# Schematic_-_EasyEDA.net
KiCad netlist of a schematic drawn in EasyEDA
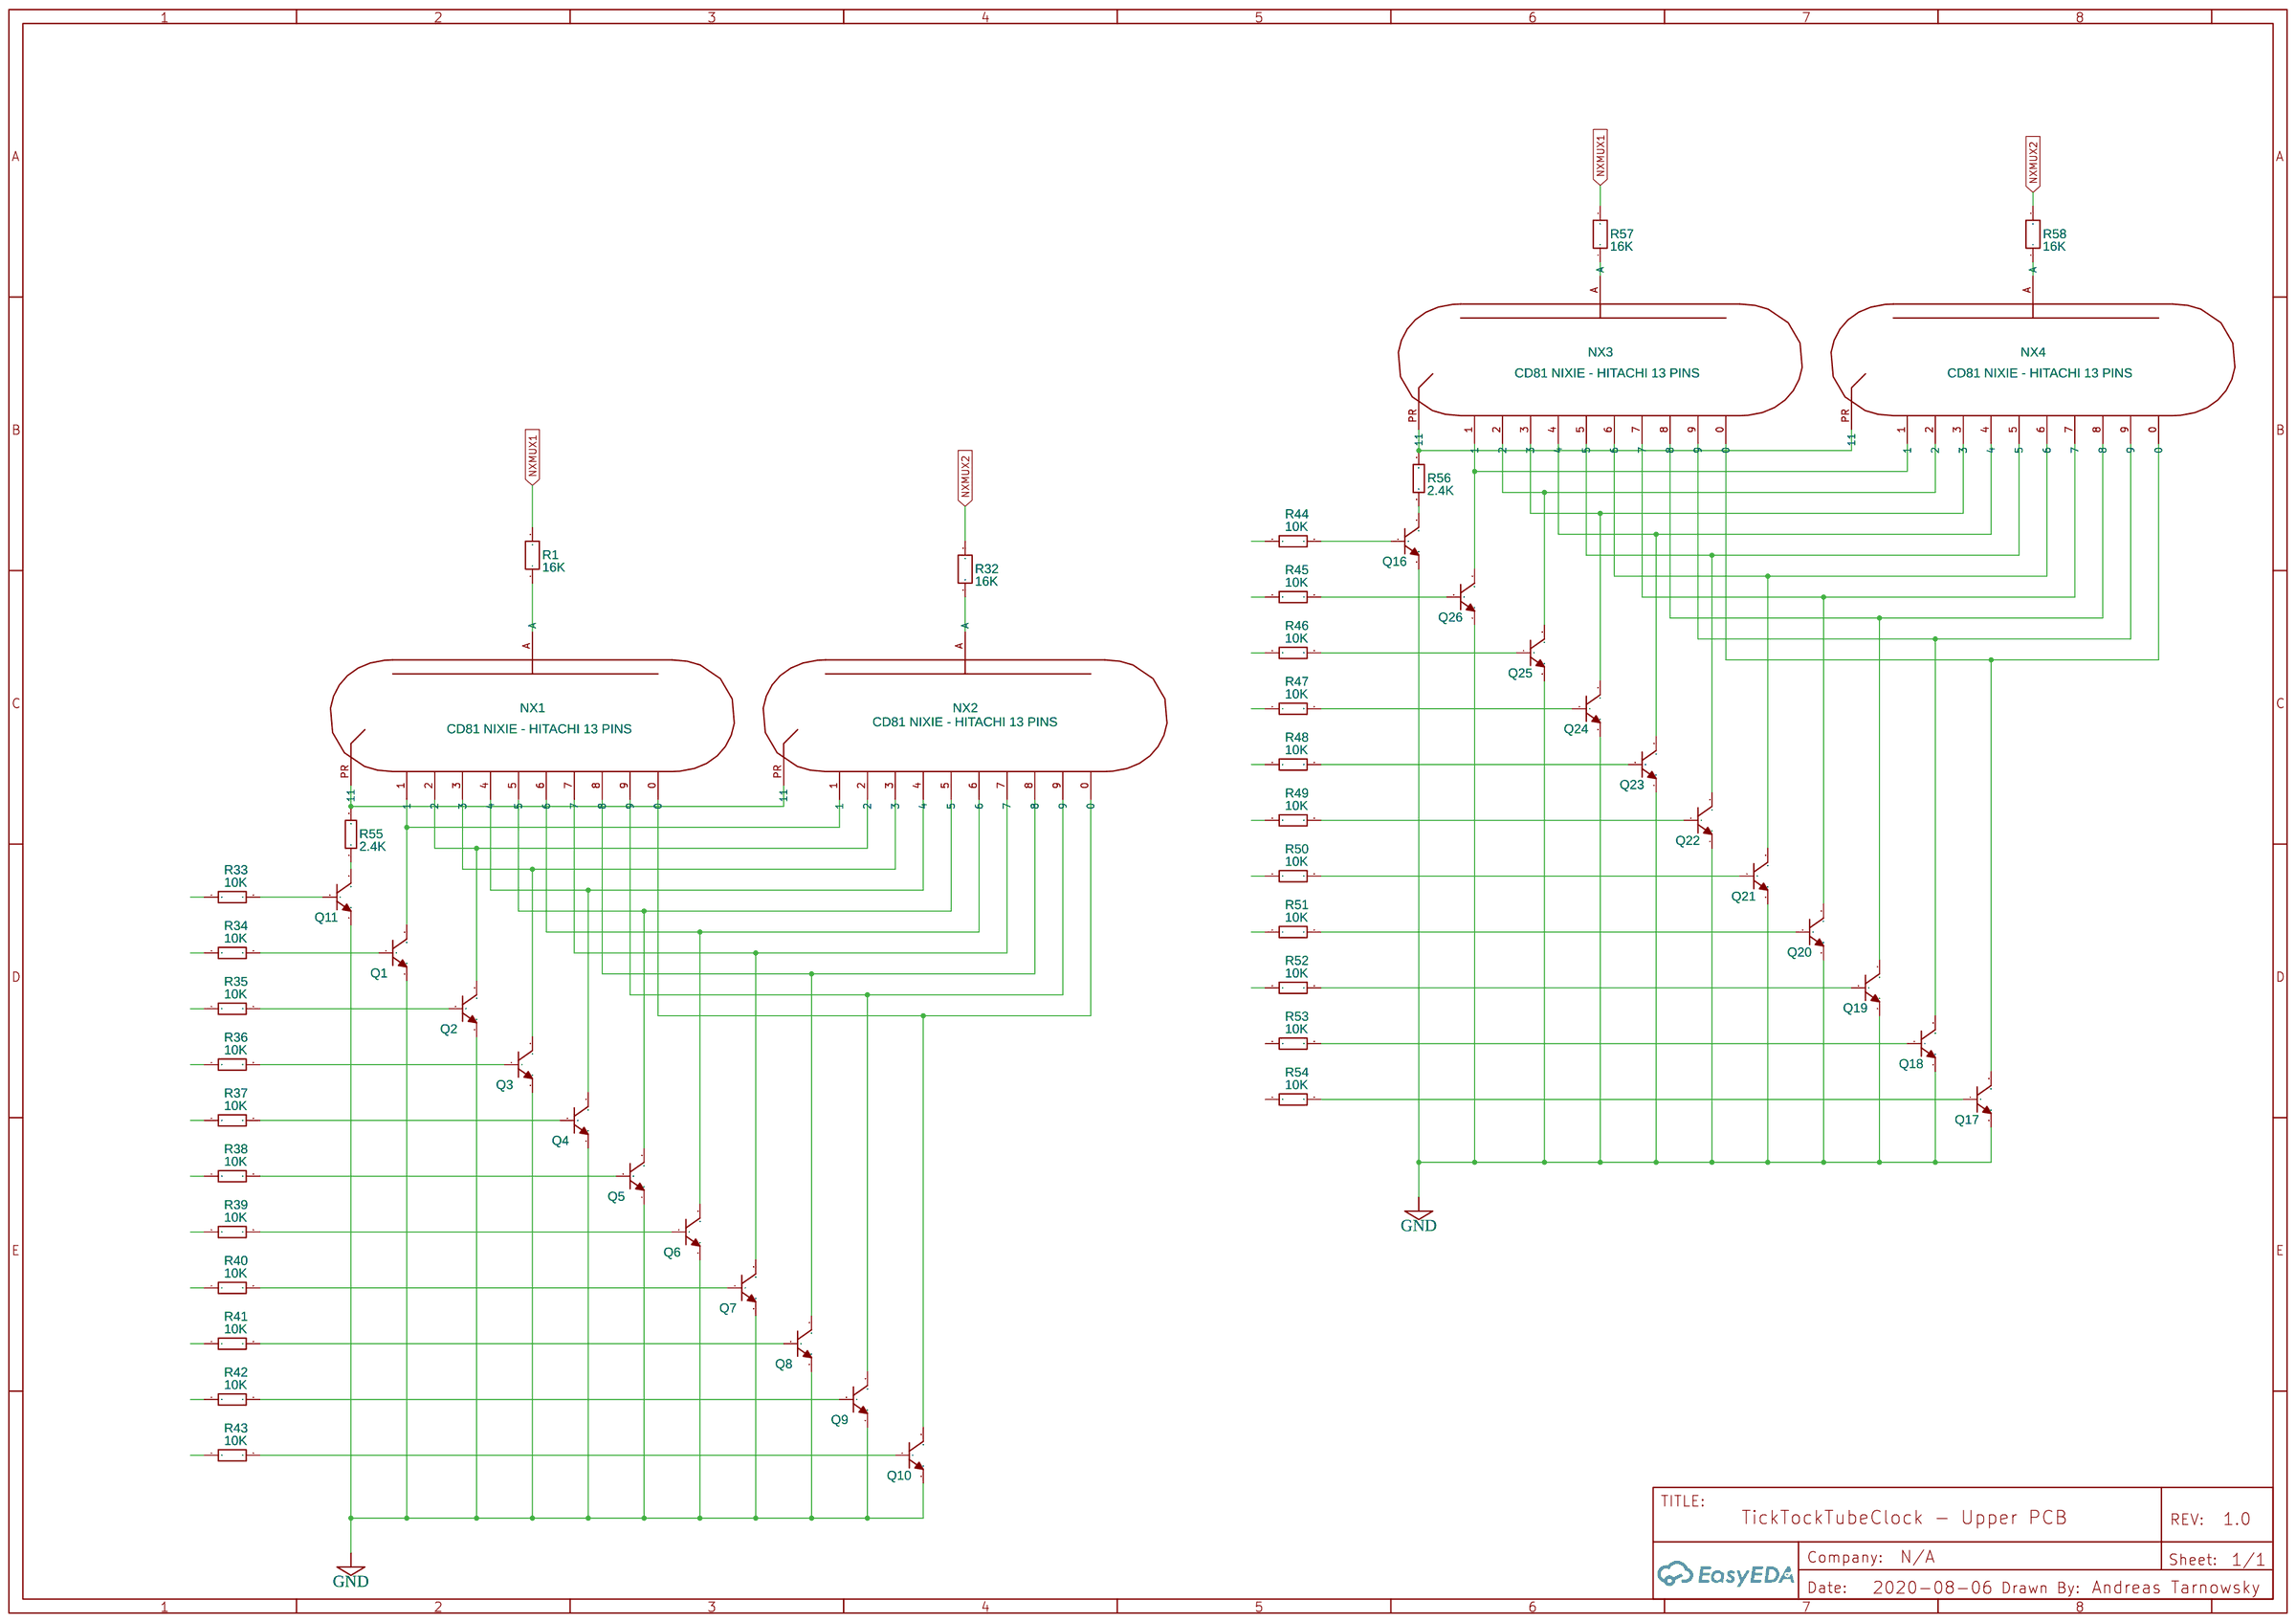
[diagram p0: Upper Schematic]
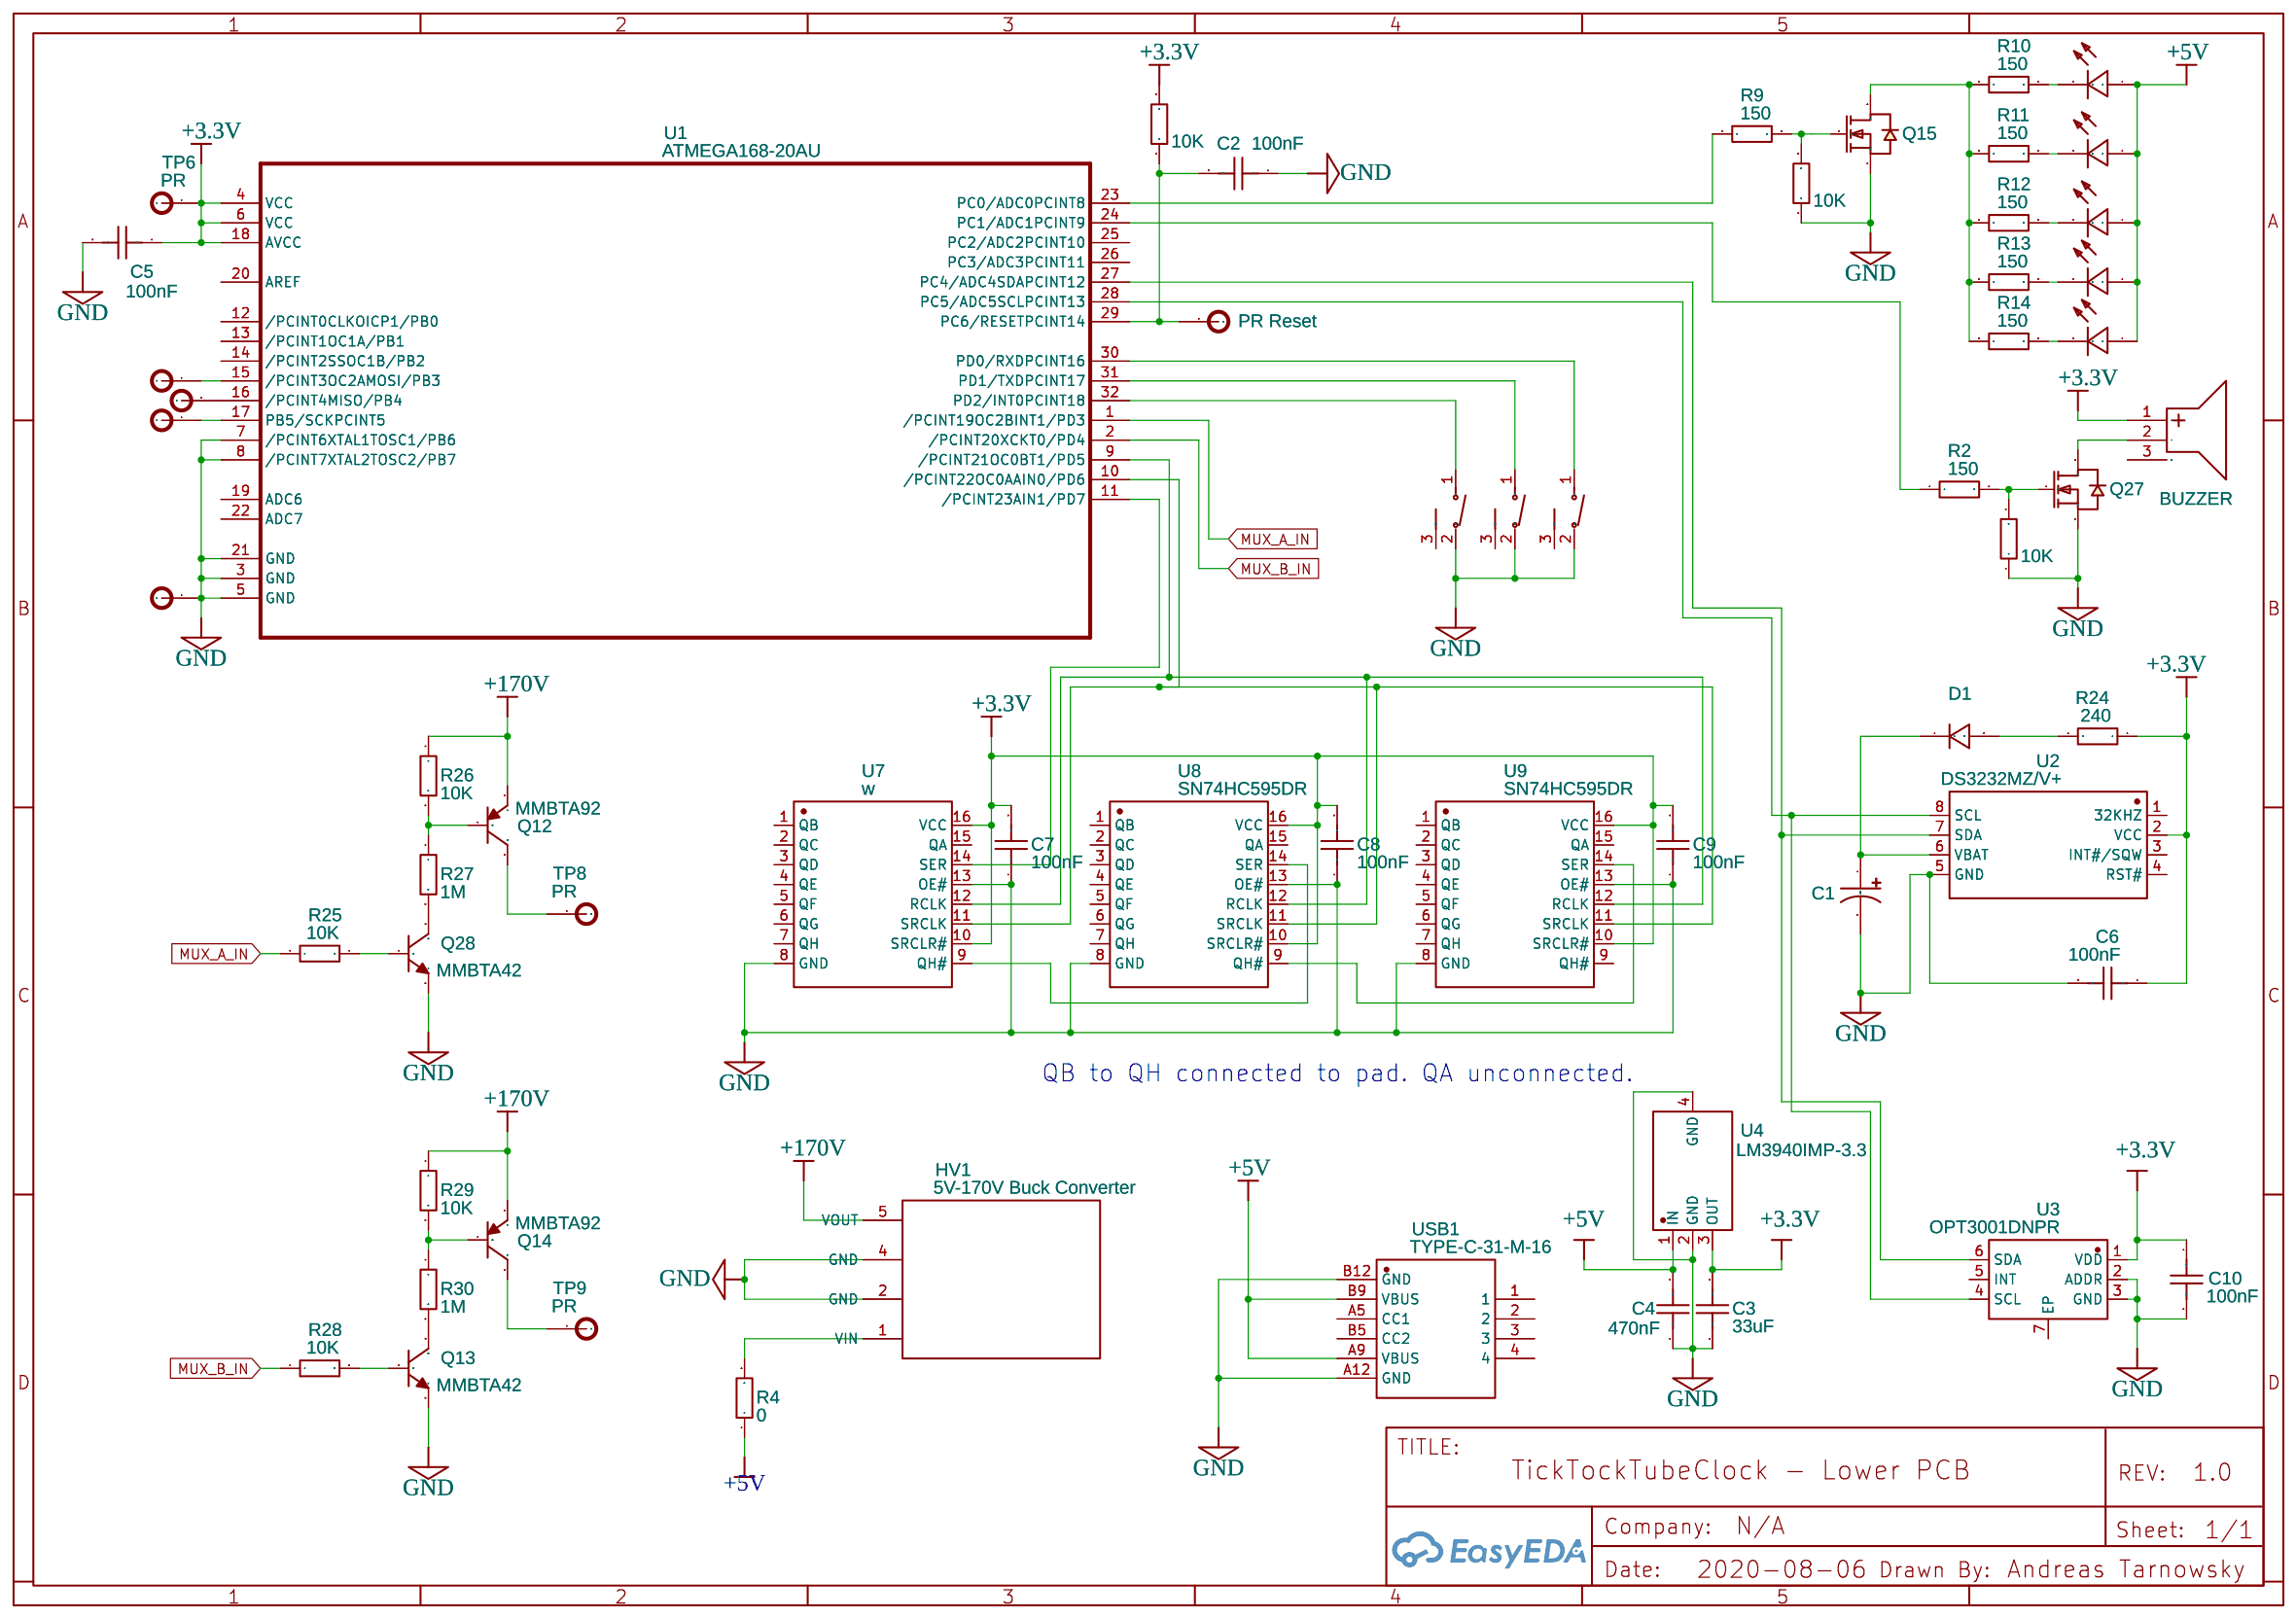
[diagram p1: Lower Schematic]

(export (version "E")
  (design (tool "Eeschema 10.0.6"))
  (components
    (comp (ref "NX1")
      (value "CD81 NIXIE - HITACHI 13 PINS")
      (libsource (lib "") (part "CD81 NIXIE - HITACHI 13 PINS"))
    )
    (comp (ref "NX2")
      (value "CD81 NIXIE - HITACHI 13 PINS")
      (libsource (lib "") (part "CD81 NIXIE - HITACHI 13 PINS"))
    )
    (comp (ref "NX3")
      (value "CD81 NIXIE - HITACHI 13 PINS")
      (libsource (lib "") (part "CD81 NIXIE - HITACHI 13 PINS"))
    )
    (comp (ref "NX4")
      (value "CD81 NIXIE - HITACHI 13 PINS")
      (libsource (lib "") (part "CD81 NIXIE - HITACHI 13 PINS"))
    )
    (comp (ref "Q1")
      (value "MMBTA42")
      (fields
        (field (name "BOM_Manufacturer Part") "MMBTA42LT1G")
        (field (name "BOM_Supplier Part") "C94389")
      )
      (libsource (lib "") (part "MMBTA42LT1G"))
    )
    (comp (ref "Q2")
      (value "MMBTA42")
      (fields
        (field (name "BOM_Manufacturer Part") "MMBTA42LT1G")
        (field (name "BOM_Supplier Part") "C94389")
      )
      (libsource (lib "") (part "MMBTA42LT1G"))
    )
    (comp (ref "Q3")
      (value "MMBTA42")
      (fields
        (field (name "BOM_Manufacturer Part") "MMBTA42LT1G")
        (field (name "BOM_Supplier Part") "C94389")
      )
      (libsource (lib "") (part "MMBTA42LT1G"))
    )
    (comp (ref "Q4")
      (value "MMBTA42")
      (fields
        (field (name "BOM_Manufacturer Part") "MMBTA42LT1G")
        (field (name "BOM_Supplier Part") "C94389")
      )
      (libsource (lib "") (part "MMBTA42LT1G"))
    )
    (comp (ref "Q5")
      (value "MMBTA42")
      (fields
        (field (name "BOM_Manufacturer Part") "MMBTA42LT1G")
        (field (name "BOM_Supplier Part") "C94389")
      )
      (libsource (lib "") (part "MMBTA42LT1G"))
    )
    (comp (ref "Q6")
      (value "MMBTA42")
      (fields
        (field (name "BOM_Manufacturer Part") "MMBTA42LT1G")
        (field (name "BOM_Supplier Part") "C94389")
      )
      (libsource (lib "") (part "MMBTA42LT1G"))
    )
    (comp (ref "Q7")
      (value "MMBTA42")
      (fields
        (field (name "BOM_Manufacturer Part") "MMBTA42LT1G")
        (field (name "BOM_Supplier Part") "C94389")
      )
      (libsource (lib "") (part "MMBTA42LT1G"))
    )
    (comp (ref "Q8")
      (value "MMBTA42")
      (fields
        (field (name "BOM_Manufacturer Part") "MMBTA42LT1G")
        (field (name "BOM_Supplier Part") "C94389")
      )
      (libsource (lib "") (part "MMBTA42LT1G"))
    )
    (comp (ref "Q9")
      (value "MMBTA42")
      (fields
        (field (name "BOM_Manufacturer Part") "MMBTA42LT1G")
        (field (name "BOM_Supplier Part") "C94389")
      )
      (libsource (lib "") (part "MMBTA42LT1G"))
    )
    (comp (ref "Q10")
      (value "MMBTA42")
      (fields
        (field (name "BOM_Manufacturer Part") "MMBTA42LT1G")
        (field (name "BOM_Supplier Part") "C94389")
      )
      (libsource (lib "") (part "MMBTA42LT1G"))
    )
    (comp (ref "Q11")
      (value "MMBTA42")
      (fields
        (field (name "BOM_Manufacturer Part") "MMBTA42LT1G")
        (field (name "BOM_Supplier Part") "C94389")
      )
      (libsource (lib "") (part "MMBTA42LT1G"))
    )
    (comp (ref "Q16")
      (value "MMBTA42")
      (fields
        (field (name "BOM_Manufacturer Part") "MMBTA42LT1G")
        (field (name "BOM_Supplier Part") "C94389")
      )
      (libsource (lib "") (part "MMBTA42LT1G"))
    )
    (comp (ref "Q17")
      (value "MMBTA42")
      (fields
        (field (name "BOM_Manufacturer Part") "MMBTA42LT1G")
        (field (name "BOM_Supplier Part") "C94389")
      )
      (libsource (lib "") (part "MMBTA42LT1G"))
    )
    (comp (ref "Q18")
      (value "MMBTA42")
      (fields
        (field (name "BOM_Manufacturer Part") "MMBTA42LT1G")
        (field (name "BOM_Supplier Part") "C94389")
      )
      (libsource (lib "") (part "MMBTA42LT1G"))
    )
    (comp (ref "Q19")
      (value "MMBTA42")
      (fields
        (field (name "BOM_Manufacturer Part") "MMBTA42LT1G")
        (field (name "BOM_Supplier Part") "C94389")
      )
      (libsource (lib "") (part "MMBTA42LT1G"))
    )
    (comp (ref "Q20")
      (value "MMBTA42")
      (fields
        (field (name "BOM_Manufacturer Part") "MMBTA42LT1G")
        (field (name "BOM_Supplier Part") "C94389")
      )
      (libsource (lib "") (part "MMBTA42LT1G"))
    )
    (comp (ref "Q21")
      (value "MMBTA42")
      (fields
        (field (name "BOM_Manufacturer Part") "MMBTA42LT1G")
        (field (name "BOM_Supplier Part") "C94389")
      )
      (libsource (lib "") (part "MMBTA42LT1G"))
    )
    (comp (ref "Q22")
      (value "MMBTA42")
      (fields
        (field (name "BOM_Manufacturer Part") "MMBTA42LT1G")
        (field (name "BOM_Supplier Part") "C94389")
      )
      (libsource (lib "") (part "MMBTA42LT1G"))
    )
    (comp (ref "Q23")
      (value "MMBTA42")
      (fields
        (field (name "BOM_Manufacturer Part") "MMBTA42LT1G")
        (field (name "BOM_Supplier Part") "C94389")
      )
      (libsource (lib "") (part "MMBTA42LT1G"))
    )
    (comp (ref "Q24")
      (value "MMBTA42")
      (fields
        (field (name "BOM_Manufacturer Part") "MMBTA42LT1G")
        (field (name "BOM_Supplier Part") "C94389")
      )
      (libsource (lib "") (part "MMBTA42LT1G"))
    )
    (comp (ref "Q25")
      (value "MMBTA42")
      (fields
        (field (name "BOM_Manufacturer Part") "MMBTA42LT1G")
        (field (name "BOM_Supplier Part") "C94389")
      )
      (libsource (lib "") (part "MMBTA42LT1G"))
    )
    (comp (ref "Q26")
      (value "MMBTA42")
      (fields
        (field (name "BOM_Manufacturer Part") "MMBTA42LT1G")
        (field (name "BOM_Supplier Part") "C94389")
      )
      (libsource (lib "") (part "MMBTA42LT1G"))
    )
    (comp (ref "R1")
      (value "16K")
      (fields
        (field (name "BOM_Manufacturer Part") "ERJ6GEYJ163V")
        (field (name "BOM_Supplier Part") "C413203")
      )
      (libsource (lib "") (part "ERJ6GEYJ163V"))
    )
    (comp (ref "R32")
      (value "16K")
      (fields
        (field (name "BOM_Manufacturer Part") "ERJ6GEYJ163V")
        (field (name "BOM_Supplier Part") "C413203")
      )
      (libsource (lib "") (part "ERJ6GEYJ163V"))
    )
    (comp (ref "R33")
      (value "10K")
      (fields
        (field (name "BOM_Manufacturer Part") "ERJPB3D1002V")
        (field (name "BOM_Supplier Part") "C189495")
      )
      (libsource (lib "") (part "ERJPB3D1002V"))
    )
    (comp (ref "R34")
      (value "10K")
      (fields
        (field (name "BOM_Manufacturer Part") "ERJPB3D1002V")
        (field (name "BOM_Supplier Part") "C189495")
      )
      (libsource (lib "") (part "ERJPB3D1002V"))
    )
    (comp (ref "R35")
      (value "10K")
      (fields
        (field (name "BOM_Manufacturer Part") "ERJPB3D1002V")
        (field (name "BOM_Supplier Part") "C189495")
      )
      (libsource (lib "") (part "ERJPB3D1002V"))
    )
    (comp (ref "R36")
      (value "10K")
      (fields
        (field (name "BOM_Manufacturer Part") "ERJPB3D1002V")
        (field (name "BOM_Supplier Part") "C189495")
      )
      (libsource (lib "") (part "ERJPB3D1002V"))
    )
    (comp (ref "R37")
      (value "10K")
      (fields
        (field (name "BOM_Manufacturer Part") "ERJPB3D1002V")
        (field (name "BOM_Supplier Part") "C189495")
      )
      (libsource (lib "") (part "ERJPB3D1002V"))
    )
    (comp (ref "R38")
      (value "10K")
      (fields
        (field (name "BOM_Manufacturer Part") "ERJPB3D1002V")
        (field (name "BOM_Supplier Part") "C189495")
      )
      (libsource (lib "") (part "ERJPB3D1002V"))
    )
    (comp (ref "R39")
      (value "10K")
      (fields
        (field (name "BOM_Manufacturer Part") "ERJPB3D1002V")
        (field (name "BOM_Supplier Part") "C189495")
      )
      (libsource (lib "") (part "ERJPB3D1002V"))
    )
    (comp (ref "R40")
      (value "10K")
      (fields
        (field (name "BOM_Manufacturer Part") "ERJPB3D1002V")
        (field (name "BOM_Supplier Part") "C189495")
      )
      (libsource (lib "") (part "ERJPB3D1002V"))
    )
    (comp (ref "R41")
      (value "10K")
      (fields
        (field (name "BOM_Manufacturer Part") "ERJPB3D1002V")
        (field (name "BOM_Supplier Part") "C189495")
      )
      (libsource (lib "") (part "ERJPB3D1002V"))
    )
    (comp (ref "R42")
      (value "10K")
      (fields
        (field (name "BOM_Manufacturer Part") "ERJPB3D1002V")
        (field (name "BOM_Supplier Part") "C189495")
      )
      (libsource (lib "") (part "ERJPB3D1002V"))
    )
    (comp (ref "R43")
      (value "10K")
      (fields
        (field (name "BOM_Manufacturer Part") "ERJPB3D1002V")
        (field (name "BOM_Supplier Part") "C189495")
      )
      (libsource (lib "") (part "ERJPB3D1002V"))
    )
    (comp (ref "R44")
      (value "10K")
      (fields
        (field (name "BOM_Manufacturer Part") "ERJPB3D1002V")
        (field (name "BOM_Supplier Part") "C189495")
      )
      (libsource (lib "") (part "ERJPB3D1002V"))
    )
    (comp (ref "R45")
      (value "10K")
      (fields
        (field (name "BOM_Manufacturer Part") "ERJPB3D1002V")
        (field (name "BOM_Supplier Part") "C189495")
      )
      (libsource (lib "") (part "ERJPB3D1002V"))
    )
    (comp (ref "R46")
      (value "10K")
      (fields
        (field (name "BOM_Manufacturer Part") "ERJPB3D1002V")
        (field (name "BOM_Supplier Part") "C189495")
      )
      (libsource (lib "") (part "ERJPB3D1002V"))
    )
    (comp (ref "R47")
      (value "10K")
      (fields
        (field (name "BOM_Manufacturer Part") "ERJPB3D1002V")
        (field (name "BOM_Supplier Part") "C189495")
      )
      (libsource (lib "") (part "ERJPB3D1002V"))
    )
    (comp (ref "R48")
      (value "10K")
      (fields
        (field (name "BOM_Manufacturer Part") "ERJPB3D1002V")
        (field (name "BOM_Supplier Part") "C189495")
      )
      (libsource (lib "") (part "ERJPB3D1002V"))
    )
    (comp (ref "R49")
      (value "10K")
      (fields
        (field (name "BOM_Manufacturer Part") "ERJPB3D1002V")
        (field (name "BOM_Supplier Part") "C189495")
      )
      (libsource (lib "") (part "ERJPB3D1002V"))
    )
    (comp (ref "R50")
      (value "10K")
      (fields
        (field (name "BOM_Manufacturer Part") "ERJPB3D1002V")
        (field (name "BOM_Supplier Part") "C189495")
      )
      (libsource (lib "") (part "ERJPB3D1002V"))
    )
    (comp (ref "R51")
      (value "10K")
      (fields
        (field (name "BOM_Manufacturer Part") "ERJPB3D1002V")
        (field (name "BOM_Supplier Part") "C189495")
      )
      (libsource (lib "") (part "ERJPB3D1002V"))
    )
    (comp (ref "R52")
      (value "10K")
      (fields
        (field (name "BOM_Manufacturer Part") "ERJPB3D1002V")
        (field (name "BOM_Supplier Part") "C189495")
      )
      (libsource (lib "") (part "ERJPB3D1002V"))
    )
    (comp (ref "R53")
      (value "10K")
      (fields
        (field (name "BOM_Manufacturer Part") "ERJPB3D1002V")
        (field (name "BOM_Supplier Part") "C189495")
      )
      (libsource (lib "") (part "ERJPB3D1002V"))
    )
    (comp (ref "R54")
      (value "10K")
      (fields
        (field (name "BOM_Manufacturer Part") "ERJPB3D1002V")
        (field (name "BOM_Supplier Part") "C189495")
      )
      (libsource (lib "") (part "ERJPB3D1002V"))
    )
    (comp (ref "R55")
      (value "2.4K")
      (fields
        (field (name "BOM_Manufacturer Part") "ERJ6RBD2401V")
        (field (name "BOM_Supplier Part") "C336868")
      )
      (libsource (lib "") (part "ERJ6RBD2401V"))
    )
    (comp (ref "R56")
      (value "2.4K")
      (fields
        (field (name "BOM_Manufacturer Part") "ERJ6RBD2401V")
        (field (name "BOM_Supplier Part") "C336868")
      )
      (libsource (lib "") (part "ERJ6RBD2401V"))
    )
    (comp (ref "R57")
      (value "16K")
      (fields
        (field (name "BOM_Manufacturer Part") "ERJ6GEYJ163V")
        (field (name "BOM_Supplier Part") "C413203")
      )
      (libsource (lib "") (part "ERJ6GEYJ163V"))
    )
    (comp (ref "R58")
      (value "16K")
      (fields
        (field (name "BOM_Manufacturer Part") "ERJ6GEYJ163V")
        (field (name "BOM_Supplier Part") "C413203")
      )
      (libsource (lib "") (part "ERJ6GEYJ163V"))
    )
    (comp (ref "BUZZER")
      (value "KLJ-5018")
      (fields (field (name "BOM_Supplier Part") "C201045"))
      (libsource (lib "") (part "KLJ-5018"))
    )
    (comp (ref "C1") (value "100mF") (libsource (lib "") (part "GOLD-CAP MATSUSHITA GC5.5V0.10F")))
    (comp (ref "C2")
      (value "100nF")
      (fields
        (field (name "BOM_Manufacturer Part") "C0603C104J5RAC")
        (field (name "BOM_Supplier Part") "C490602")
      )
      (libsource (lib "") (part "C0603C104J5RAC_2"))
    )
    (comp (ref "C3")
      (value "33uF")
      (fields
        (field (name "BOM_Manufacturer Part") "C3216X5R1A336MTJ00N")
        (field (name "BOM_Supplier Part") "C342606")
      )
      (libsource (lib "") (part "C3216X5R1A336MTJ00N"))
    )
    (comp (ref "C4")
      (value "470nF")
      (fields
        (field (name "BOM_Manufacturer Part") "GCM21BR71H474MA55L")
        (field (name "BOM_Supplier Part") "C161264")
      )
      (libsource (lib "") (part "GCM21BR71H474MA55L"))
    )
    (comp (ref "C5")
      (value "100nF")
      (fields
        (field (name "BOM_Manufacturer Part") "C0603C104J5RAC")
        (field (name "BOM_Supplier Part") "C490602")
      )
      (libsource (lib "") (part "C0603C104J5RAC_2"))
    )
    (comp (ref "C6")
      (value "100nF")
      (fields
        (field (name "BOM_Manufacturer Part") "C0603C104J5RAC")
        (field (name "BOM_Supplier Part") "C490602")
      )
      (libsource (lib "") (part "C0603C104J5RAC"))
    )
    (comp (ref "C7")
      (value "100nF")
      (fields
        (field (name "BOM_Manufacturer Part") "C0603C104J5RAC")
        (field (name "BOM_Supplier Part") "C490602")
      )
      (libsource (lib "") (part "C0603C104J5RAC_3"))
    )
    (comp (ref "C8")
      (value "100nF")
      (fields
        (field (name "BOM_Manufacturer Part") "C0603C104J5RAC")
        (field (name "BOM_Supplier Part") "C490602")
      )
      (libsource (lib "") (part "C0603C104J5RAC_3"))
    )
    (comp (ref "C9")
      (value "100nF")
      (fields
        (field (name "BOM_Manufacturer Part") "C0603C104J5RAC")
        (field (name "BOM_Supplier Part") "C490602")
      )
      (libsource (lib "") (part "C0603C104J5RAC_3"))
    )
    (comp (ref "C10")
      (value "100nF")
      (fields
        (field (name "BOM_Manufacturer Part") "C0603C104J5RAC")
        (field (name "BOM_Supplier Part") "C490602")
      )
      (libsource (lib "") (part "C0603C104J5RAC_1"))
    )
    (comp (ref "D1")
      (value "1N4148W-13-F")
      (fields (field (name "BOM_Supplier Part") "C112342"))
      (libsource (lib "") (part "1N4148W-13-F"))
    )
    (comp (ref "HV1") (value "5V-170V Buck Converter") (libsource (lib "") (part "5V-170V Buck Converter")))
    (comp (ref "LED1")
      (value "17-21/S2C-FR1S2L/3T")
      (fields (field (name "BOM_Supplier Part") "C264419"))
      (libsource (lib "") (part "17-21/S2C-FR1S2L/3T"))
    )
    (comp (ref "LED2")
      (value "17-21/S2C-FR1S2L/3T")
      (fields (field (name "BOM_Supplier Part") "C264419"))
      (libsource (lib "") (part "17-21/S2C-FR1S2L/3T"))
    )
    (comp (ref "LED3")
      (value "17-21/S2C-FR1S2L/3T")
      (fields (field (name "BOM_Supplier Part") "C264419"))
      (libsource (lib "") (part "17-21/S2C-FR1S2L/3T"))
    )
    (comp (ref "LED4")
      (value "17-21/S2C-FR1S2L/3T")
      (fields (field (name "BOM_Supplier Part") "C264419"))
      (libsource (lib "") (part "17-21/S2C-FR1S2L/3T"))
    )
    (comp (ref "LED5")
      (value "17-21/S2C-FR1S2L/3T")
      (fields (field (name "BOM_Supplier Part") "C264419"))
      (libsource (lib "") (part "17-21/S2C-FR1S2L/3T"))
    )
    (comp (ref "Q12")
      (value "MMBTA92")
      (fields (field (name "BOM_Manufacturer Part") "MMBTA92 2D") (field (name "BOM_Supplier Part") "C8516"))
      (libsource (lib "") (part "MMBTA92 2D"))
    )
    (comp (ref "Q13")
      (value "MMBTA42")
      (fields (field (name "BOM_Supplier Part") "C8515"))
      (libsource (lib "") (part "MMBTA42_C8515"))
    )
    (comp (ref "Q14")
      (value "MMBTA92")
      (fields (field (name "BOM_Manufacturer Part") "MMBTA92 2D") (field (name "BOM_Supplier Part") "C8516"))
      (libsource (lib "") (part "MMBTA92 2D"))
    )
    (comp (ref "Q15")
      (value "IRLML2502TRPBF")
      (fields (field (name "BOM_Supplier Part") "C2589"))
      (libsource (lib "") (part "IRLML2502TRPBF"))
    )
    (comp (ref "Q27")
      (value "IRLML2502TRPBF")
      (fields (field (name "BOM_Supplier Part") "C2589"))
      (libsource (lib "") (part "IRLML2502TRPBF"))
    )
    (comp (ref "Q28")
      (value "MMBTA42")
      (fields (field (name "BOM_Supplier Part") "C8515"))
      (libsource (lib "") (part "MMBTA42_C8515"))
    )
    (comp (ref "R2")
      (value "150")
      (fields
        (field (name "BOM_Manufacturer Part") "RMC08051501%N")
        (field (name "BOM_Supplier Part") "C325766")
      )
      (libsource (lib "") (part "RMC08051501%N"))
    )
    (comp (ref "R3")
      (value "10K")
      (fields
        (field (name "BOM_Manufacturer Part") "0805W8F1002T5E")
        (field (name "BOM_Supplier Part") "C17414")
      )
      (libsource (lib "") (part "0805W8F1002T5E_1"))
    )
    (comp (ref "R4")
      (value "0")
      (fields
        (field (name "BOM_Manufacturer Part") "0805W8F1002T5E")
        (field (name "BOM_Supplier Part") "C17414")
      )
      (libsource (lib "") (part "0805W8F1002T5E_1"))
    )
    (comp (ref "R5")
      (value "10K")
      (fields
        (field (name "BOM_Manufacturer Part") "0805W8F1002T5E")
        (field (name "BOM_Supplier Part") "C17414")
      )
      (libsource (lib "") (part "0805W8F1002T5E_1"))
    )
    (comp (ref "R8")
      (value "10K")
      (fields
        (field (name "BOM_Manufacturer Part") "0805W8F1002T5E")
        (field (name "BOM_Supplier Part") "C17414")
      )
      (libsource (lib "") (part "0805W8F1002T5E_1"))
    )
    (comp (ref "R9")
      (value "150")
      (fields
        (field (name "BOM_Manufacturer Part") "RMC08051501%N")
        (field (name "BOM_Supplier Part") "C325766")
      )
      (libsource (lib "") (part "RMC08051501%N"))
    )
    (comp (ref "R10")
      (value "150")
      (fields
        (field (name "BOM_Manufacturer Part") "RMC08051501%N")
        (field (name "BOM_Supplier Part") "C325766")
      )
      (libsource (lib "") (part "RMC08051501%N"))
    )
    (comp (ref "R11")
      (value "150")
      (fields
        (field (name "BOM_Manufacturer Part") "RMC08051501%N")
        (field (name "BOM_Supplier Part") "C325766")
      )
      (libsource (lib "") (part "RMC08051501%N"))
    )
    (comp (ref "R12")
      (value "150")
      (fields
        (field (name "BOM_Manufacturer Part") "RMC08051501%N")
        (field (name "BOM_Supplier Part") "C325766")
      )
      (libsource (lib "") (part "RMC08051501%N"))
    )
    (comp (ref "R13")
      (value "150")
      (fields
        (field (name "BOM_Manufacturer Part") "RMC08051501%N")
        (field (name "BOM_Supplier Part") "C325766")
      )
      (libsource (lib "") (part "RMC08051501%N"))
    )
    (comp (ref "R14")
      (value "150")
      (fields
        (field (name "BOM_Manufacturer Part") "RMC08051501%N")
        (field (name "BOM_Supplier Part") "C325766")
      )
      (libsource (lib "") (part "RMC08051501%N"))
    )
    (comp (ref "R24")
      (value "240")
      (fields
        (field (name "BOM_Manufacturer Part") "0805W8F2400T5E")
        (field (name "BOM_Supplier Part") "C17572")
      )
      (libsource (lib "") (part "0805W8F2400T5E"))
    )
    (comp (ref "R25")
      (value "10K")
      (fields
        (field (name "BOM_Manufacturer Part") "0805W8F1002T5E")
        (field (name "BOM_Supplier Part") "C17414")
      )
      (libsource (lib "") (part "0805W8F1002T5E_2"))
    )
    (comp (ref "R26")
      (value "10K")
      (fields
        (field (name "BOM_Manufacturer Part") "0805W8F1002T5E")
        (field (name "BOM_Supplier Part") "C17414")
      )
      (libsource (lib "") (part "0805W8F1002T5E"))
    )
    (comp (ref "R27")
      (value "1M")
      (fields
        (field (name "BOM_Manufacturer Part") "0805W8F1004T5E")
        (field (name "BOM_Supplier Part") "C17514")
      )
      (libsource (lib "") (part "0805W8F1002T5E"))
    )
    (comp (ref "R28")
      (value "10K")
      (fields
        (field (name "BOM_Manufacturer Part") "0805W8F1002T5E")
        (field (name "BOM_Supplier Part") "C17414")
      )
      (libsource (lib "") (part "0805W8F1002T5E_2"))
    )
    (comp (ref "R29")
      (value "10K")
      (fields
        (field (name "BOM_Manufacturer Part") "0805W8F1002T5E")
        (field (name "BOM_Supplier Part") "C17414")
      )
      (libsource (lib "") (part "0805W8F1002T5E"))
    )
    (comp (ref "R30")
      (value "1M")
      (fields
        (field (name "BOM_Manufacturer Part") "0805W8F1004T5E")
        (field (name "BOM_Supplier Part") "C17514")
      )
      (libsource (lib "") (part "0805W8F1002T5E"))
    )
    (comp (ref "SW1")
      (value "TCD-C2KQR")
      (fields (field (name "BOM_Supplier Part") "C483805"))
      (libsource (lib "") (part "TCD-C2KQR"))
    )
    (comp (ref "SW2")
      (value "TCD-C2KQR")
      (fields (field (name "BOM_Supplier Part") "C483805"))
      (libsource (lib "") (part "TCD-C2KQR"))
    )
    (comp (ref "SW3")
      (value "TCD-C2KQR")
      (fields (field (name "BOM_Supplier Part") "C483805"))
      (libsource (lib "") (part "TCD-C2KQR"))
    )
    (comp (ref "TP1")
      (value "PR Reset")
      (fields (field (name "BOM_Manufacturer Part") "Test_Pin"))
      (libsource (lib "") (part "Test Point Small"))
    )
    (comp (ref "TP3")
      (value "PR")
      (fields (field (name "BOM_Manufacturer Part") "Test_Pin"))
      (libsource (lib "") (part "Test Point Small_1"))
    )
    (comp (ref "TP4")
      (value "PR")
      (fields (field (name "BOM_Manufacturer Part") "Test_Pin"))
      (libsource (lib "") (part "Test Point Small_1"))
    )
    (comp (ref "TP5")
      (value "PR")
      (fields (field (name "BOM_Manufacturer Part") "Test_Pin"))
      (libsource (lib "") (part "Test Point Small_1"))
    )
    (comp (ref "TP6")
      (value "PR")
      (fields (field (name "BOM_Manufacturer Part") "Test_Pin"))
      (libsource (lib "") (part "Test Point Small_1"))
    )
    (comp (ref "TP7")
      (value "PR")
      (fields (field (name "BOM_Manufacturer Part") "Test_Pin"))
      (libsource (lib "") (part "Test Point Small_1"))
    )
    (comp (ref "TP8")
      (value "PR")
      (fields (field (name "BOM_Manufacturer Part") "Test_Pin"))
      (libsource (lib "") (part "Test Point Small"))
    )
    (comp (ref "TP9")
      (value "PR")
      (fields (field (name "BOM_Manufacturer Part") "Test_Pin"))
      (libsource (lib "") (part "Test Point Small"))
    )
    (comp (ref "U1") (value "ATMEGA168-20AU") (libsource (lib "") (part "ATMEGA168-20AU")))
    (comp (ref "U2")
      (value "DS3232MZ/V+")
      (fields (field (name "BOM_Supplier Part") "C143316"))
      (libsource (lib "") (part "DS3232MZ/V+"))
    )
    (comp (ref "U3")
      (value "OPT3001DNPR")
      (fields (field (name "BOM_Supplier Part") "C90462"))
      (libsource (lib "") (part "OPT3001DNPR"))
    )
    (comp (ref "U4")
      (value "LM3940IMP-3.3")
      (fields
        (field (name "BOM_Manufacturer Part") "LM3940IMP-3.3/NOPB")
        (field (name "BOM_Supplier Part") "C140319")
      )
      (libsource (lib "") (part "LM3940IMP-3.3/NOPB"))
    )
    (comp (ref "U7")
      (value "w")
      (fields
        (field (name "BOM_Manufacturer Part") "SN74HC595DR")
        (field (name "BOM_Supplier Part") "C10092")
      )
      (libsource (lib "") (part "SN74HC595DR"))
    )
    (comp (ref "U8")
      (value "SN74HC595DR")
      (fields (field (name "BOM_Supplier Part") "C10092"))
      (libsource (lib "") (part "SN74HC595DR"))
    )
    (comp (ref "U9")
      (value "SN74HC595DR")
      (fields (field (name "BOM_Supplier Part") "C10092"))
      (libsource (lib "") (part "SN74HC595DR"))
    )
    (comp (ref "USB1")
      (value "TYPE-C-31-M-16")
      (fields (field (name "BOM_Supplier Part") "C283541"))
      (libsource (lib "") (part "TYPE-C-31-M-16"))
    )
  )
  (nets
    (net (code "1") (name "+3.3V") (class "Default")
      (node (ref "BUZZER") (pin "1") (pinfunction "+_1") (pintype "unspecified"))
      (node (ref "C10") (pin "1") (pinfunction "1_1") (pintype "unspecified"))
      (node (ref "C3") (pin "2") (pinfunction "2_2") (pintype "unspecified"))
      (node (ref "C5") (pin "1") (pinfunction "1_1") (pintype "unspecified"))
      (node (ref "C6") (pin "1") (pinfunction "1_1") (pintype "unspecified"))
      (node (ref "C7") (pin "2") (pinfunction "2_2") (pintype "unspecified"))
      (node (ref "C8") (pin "2") (pinfunction "2_2") (pintype "unspecified"))
      (node (ref "C9") (pin "2") (pinfunction "2_2") (pintype "unspecified"))
      (node (ref "R24") (pin "1") (pinfunction "1_1") (pintype "input"))
      (node (ref "R5") (pin "2") (pinfunction "2_2") (pintype "input"))
      (node (ref "TP6") (pin "1") (pinfunction "1_1") (pintype "unspecified"))
      (node (ref "U1") (pin "18") (pinfunction "AVCC_18") (pintype "passive"))
      (node (ref "U1") (pin "4") (pinfunction "VCC_4") (pintype "passive"))
      (node (ref "U1") (pin "6") (pinfunction "VCC_6") (pintype "passive"))
      (node (ref "U2") (pin "2") (pinfunction "VCC_2") (pintype "unspecified"))
      (node (ref "U3") (pin "1") (pinfunction "VDD_1") (pintype "unspecified"))
      (node (ref "U4") (pin "3") (pinfunction "OUT_3") (pintype "unspecified"))
      (node (ref "U7") (pin "10") (pinfunction "SRCLR#_10") (pintype "unspecified"))
      (node (ref "U7") (pin "16") (pinfunction "VCC_16") (pintype "unspecified"))
      (node (ref "U8") (pin "10") (pinfunction "SRCLR#_10") (pintype "unspecified"))
      (node (ref "U8") (pin "16") (pinfunction "VCC_16") (pintype "unspecified"))
      (node (ref "U9") (pin "10") (pinfunction "SRCLR#_10") (pintype "unspecified"))
      (node (ref "U9") (pin "16") (pinfunction "VCC_16") (pintype "unspecified"))
    )
    (net (code "2") (name "+5V") (class "Default")
      (node (ref "C4") (pin "2") (pinfunction "2_2") (pintype "unspecified"))
      (node (ref "LED1") (pin "1") (pinfunction "A_1") (pintype "unspecified"))
      (node (ref "LED2") (pin "1") (pinfunction "A_1") (pintype "unspecified"))
      (node (ref "LED3") (pin "1") (pinfunction "A_1") (pintype "unspecified"))
      (node (ref "LED4") (pin "1") (pinfunction "A_1") (pintype "unspecified"))
      (node (ref "LED5") (pin "1") (pinfunction "A_1") (pintype "unspecified"))
      (node (ref "R4") (pin "1") (pinfunction "1_1") (pintype "input"))
      (node (ref "U4") (pin "1") (pinfunction "IN_1") (pintype "unspecified"))
      (node (ref "USB1") (pin "A9") (pinfunction "VBUS_A9") (pintype "unspecified"))
      (node (ref "USB1") (pin "B9") (pinfunction "VBUS_B9") (pintype "unspecified"))
    )
    (net (code "3") (name "+170V") (class "Default")
      (node (ref "HV1") (pin "5") (pinfunction "VOUT_5") (pintype "unspecified"))
      (node (ref "Q12") (pin "2") (pinfunction "E_2") (pintype "unspecified"))
      (node (ref "Q14") (pin "2") (pinfunction "E_2") (pintype "unspecified"))
      (node (ref "R26") (pin "1") (pinfunction "1_1") (pintype "input"))
      (node (ref "R29") (pin "1") (pinfunction "1_1") (pintype "input"))
    )
    (net (code "4") (name "GND") (class "Default")
      (node (ref "C1") (pin "2") (pinfunction "2_2") (pintype "unspecified"))
      (node (ref "C10") (pin "2") (pinfunction "2_2") (pintype "unspecified"))
      (node (ref "C2") (pin "1") (pinfunction "1_1") (pintype "unspecified"))
      (node (ref "C3") (pin "1") (pinfunction "1_1") (pintype "unspecified"))
      (node (ref "C4") (pin "1") (pinfunction "1_1") (pintype "unspecified"))
      (node (ref "C5") (pin "2") (pinfunction "2_2") (pintype "unspecified"))
      (node (ref "C6") (pin "2") (pinfunction "2_2") (pintype "unspecified"))
      (node (ref "C7") (pin "1") (pinfunction "1_1") (pintype "unspecified"))
      (node (ref "C8") (pin "1") (pinfunction "1_1") (pintype "unspecified"))
      (node (ref "C9") (pin "1") (pinfunction "1_1") (pintype "unspecified"))
      (node (ref "HV1") (pin "2") (pinfunction "GND_2") (pintype "unspecified"))
      (node (ref "HV1") (pin "4") (pinfunction "GND_4") (pintype "unspecified"))
      (node (ref "Q1") (pin "2") (pinfunction "2_2") (pintype "input"))
      (node (ref "Q10") (pin "2") (pinfunction "2_2") (pintype "input"))
      (node (ref "Q11") (pin "2") (pinfunction "2_2") (pintype "input"))
      (node (ref "Q13") (pin "2") (pinfunction "E_2") (pintype "unspecified"))
      (node (ref "Q15") (pin "2") (pinfunction "S_2") (pintype "unspecified"))
      (node (ref "Q16") (pin "2") (pinfunction "2_2") (pintype "input"))
      (node (ref "Q17") (pin "2") (pinfunction "2_2") (pintype "input"))
      (node (ref "Q18") (pin "2") (pinfunction "2_2") (pintype "input"))
      (node (ref "Q19") (pin "2") (pinfunction "2_2") (pintype "input"))
      (node (ref "Q2") (pin "2") (pinfunction "2_2") (pintype "input"))
      (node (ref "Q20") (pin "2") (pinfunction "2_2") (pintype "input"))
      (node (ref "Q21") (pin "2") (pinfunction "2_2") (pintype "input"))
      (node (ref "Q22") (pin "2") (pinfunction "2_2") (pintype "input"))
      (node (ref "Q23") (pin "2") (pinfunction "2_2") (pintype "input"))
      (node (ref "Q24") (pin "2") (pinfunction "2_2") (pintype "input"))
      (node (ref "Q25") (pin "2") (pinfunction "2_2") (pintype "input"))
      (node (ref "Q26") (pin "2") (pinfunction "2_2") (pintype "input"))
      (node (ref "Q27") (pin "2") (pinfunction "S_2") (pintype "unspecified"))
      (node (ref "Q28") (pin "2") (pinfunction "E_2") (pintype "unspecified"))
      (node (ref "Q3") (pin "2") (pinfunction "2_2") (pintype "input"))
      (node (ref "Q4") (pin "2") (pinfunction "2_2") (pintype "input"))
      (node (ref "Q5") (pin "2") (pinfunction "2_2") (pintype "input"))
      (node (ref "Q6") (pin "2") (pinfunction "2_2") (pintype "input"))
      (node (ref "Q7") (pin "2") (pinfunction "2_2") (pintype "input"))
      (node (ref "Q8") (pin "2") (pinfunction "2_2") (pintype "input"))
      (node (ref "Q9") (pin "2") (pinfunction "2_2") (pintype "input"))
      (node (ref "R3") (pin "1") (pinfunction "1_1") (pintype "input"))
      (node (ref "R8") (pin "1") (pinfunction "1_1") (pintype "input"))
      (node (ref "SW1") (pin "2") (pinfunction "2_2") (pintype "unspecified"))
      (node (ref "SW2") (pin "2") (pinfunction "2_2") (pintype "unspecified"))
      (node (ref "SW3") (pin "2") (pinfunction "2_2") (pintype "unspecified"))
      (node (ref "TP7") (pin "1") (pinfunction "1_1") (pintype "unspecified"))
      (node (ref "U1") (pin "21") (pinfunction "GND_21") (pintype "unspecified"))
      (node (ref "U1") (pin "3") (pinfunction "GND_3") (pintype "unspecified"))
      (node (ref "U1") (pin "5") (pinfunction "GND_5") (pintype "unspecified"))
      (node (ref "U1") (pin "7") (pinfunction "/PCINT6XTAL1TOSC1/PB6_7") (pintype "unspecified"))
      (node (ref "U1") (pin "8") (pinfunction "/PCINT7XTAL2TOSC2/PB7_8") (pintype "unspecified"))
      (node (ref "U2") (pin "5") (pinfunction "GND_5") (pintype "unspecified"))
      (node (ref "U3") (pin "2") (pinfunction "ADDR_2") (pintype "unspecified"))
      (node (ref "U3") (pin "3") (pinfunction "GND_3") (pintype "unspecified"))
      (node (ref "U4") (pin "2") (pinfunction "GND_2") (pintype "unspecified"))
      (node (ref "U4") (pin "4") (pinfunction "GND_4") (pintype "unspecified"))
      (node (ref "U7") (pin "13") (pinfunction "OE#_13") (pintype "unspecified"))
      (node (ref "U7") (pin "8") (pinfunction "GND_8") (pintype "unspecified"))
      (node (ref "U8") (pin "13") (pinfunction "OE#_13") (pintype "unspecified"))
      (node (ref "U8") (pin "8") (pinfunction "GND_8") (pintype "unspecified"))
      (node (ref "U9") (pin "13") (pinfunction "OE#_13") (pintype "unspecified"))
      (node (ref "U9") (pin "8") (pinfunction "GND_8") (pintype "unspecified"))
      (node (ref "USB1") (pin "A12") (pinfunction "GND_A12") (pintype "unspecified"))
      (node (ref "USB1") (pin "B12") (pinfunction "GND_B12") (pintype "unspecified"))
    )
    (net (code "5") (name "MUX_A_IN") (class "Default")
      (node (ref "R25") (pin "1") (pinfunction "1_1") (pintype "input"))
      (node (ref "U1") (pin "1") (pinfunction "/PCINT19OC2BINT1/PD3_1") (pintype "unspecified"))
    )
    (net (code "6") (name "MUX_B_IN") (class "Default")
      (node (ref "R28") (pin "1") (pinfunction "1_1") (pintype "input"))
      (node (ref "U1") (pin "2") (pinfunction "/PCINT20XCKT0/PD4_2") (pintype "unspecified"))
    )
    (net (code "7") (name "NXMUX1") (class "Default")
      (node (ref "R1") (pin "2") (pinfunction "2_2") (pintype "unspecified"))
      (node (ref "R57") (pin "2") (pinfunction "2_2") (pintype "unspecified"))
    )
    (net (code "8") (name "NXMUX2") (class "Default")
      (node (ref "R32") (pin "2") (pinfunction "2_2") (pintype "unspecified"))
      (node (ref "R58") (pin "2") (pinfunction "2_2") (pintype "unspecified"))
    )
    (net (code "9") (name "Net-(BUZZER--)") (class "Default")
      (node (ref "BUZZER") (pin "2") (pinfunction "-_2") (pintype "unspecified"))
      (node (ref "Q27") (pin "3") (pinfunction "D_3") (pintype "unspecified"))
    )
    (net (code "10") (name "Net-(D1-Pad2)") (class "Default")
      (node (ref "D1") (pin "2") (pinfunction "2_2") (pintype "unspecified"))
      (node (ref "R24") (pin "2") (pinfunction "2_2") (pintype "input"))
    )
    (net (code "11") (name "Net-(HV1-VIN)") (class "Default")
      (node (ref "HV1") (pin "1") (pinfunction "VIN_1") (pintype "unspecified"))
      (node (ref "R4") (pin "2") (pinfunction "2_2") (pintype "input"))
    )
    (net (code "12") (name "Net-(LED1-K)") (class "Default")
      (node (ref "LED1") (pin "2") (pinfunction "K_2") (pintype "unspecified"))
      (node (ref "R10") (pin "2") (pinfunction "2_2") (pintype "unspecified"))
    )
    (net (code "13") (name "Net-(LED2-K)") (class "Default")
      (node (ref "LED2") (pin "2") (pinfunction "K_2") (pintype "unspecified"))
      (node (ref "R11") (pin "2") (pinfunction "2_2") (pintype "unspecified"))
    )
    (net (code "14") (name "Net-(LED3-K)") (class "Default")
      (node (ref "LED3") (pin "2") (pinfunction "K_2") (pintype "unspecified"))
      (node (ref "R12") (pin "2") (pinfunction "2_2") (pintype "unspecified"))
    )
    (net (code "15") (name "Net-(LED4-K)") (class "Default")
      (node (ref "LED4") (pin "2") (pinfunction "K_2") (pintype "unspecified"))
      (node (ref "R13") (pin "2") (pinfunction "2_2") (pintype "unspecified"))
    )
    (net (code "16") (name "Net-(LED5-K)") (class "Default")
      (node (ref "LED5") (pin "2") (pinfunction "K_2") (pintype "unspecified"))
      (node (ref "R14") (pin "2") (pinfunction "2_2") (pintype "unspecified"))
    )
    (net (code "17") (name "Net-(NX1-11)") (class "Default")
      (node (ref "NX1") (pin "PR") (pinfunction "11_PR") (pintype "unspecified"))
      (node (ref "NX2") (pin "PR") (pinfunction "11_PR") (pintype "unspecified"))
      (node (ref "R55") (pin "2") (pinfunction "2_2") (pintype "unspecified"))
    )
    (net (code "18") (name "Net-(NX1-Pad0)") (class "Default")
      (node (ref "NX1") (pin "0") (pinfunction "0_0") (pintype "unspecified"))
      (node (ref "NX2") (pin "0") (pinfunction "0_0") (pintype "unspecified"))
      (node (ref "Q10") (pin "3") (pinfunction "3_3") (pintype "input"))
    )
    (net (code "19") (name "Net-(NX1-Pad1)") (class "Default")
      (node (ref "NX1") (pin "1") (pinfunction "1_1") (pintype "unspecified"))
      (node (ref "NX2") (pin "1") (pinfunction "1_1") (pintype "unspecified"))
      (node (ref "Q1") (pin "3") (pinfunction "3_3") (pintype "input"))
    )
    (net (code "20") (name "Net-(NX1-Pad2)") (class "Default")
      (node (ref "NX1") (pin "2") (pinfunction "2_2") (pintype "unspecified"))
      (node (ref "NX2") (pin "2") (pinfunction "2_2") (pintype "unspecified"))
      (node (ref "Q2") (pin "3") (pinfunction "3_3") (pintype "input"))
    )
    (net (code "21") (name "Net-(NX1-Pad3)") (class "Default")
      (node (ref "NX1") (pin "3") (pinfunction "3_3") (pintype "unspecified"))
      (node (ref "NX2") (pin "3") (pinfunction "3_3") (pintype "unspecified"))
      (node (ref "Q3") (pin "3") (pinfunction "3_3") (pintype "input"))
    )
    (net (code "22") (name "Net-(NX1-Pad4)") (class "Default")
      (node (ref "NX1") (pin "4") (pinfunction "4_4") (pintype "unspecified"))
      (node (ref "NX2") (pin "4") (pinfunction "4_4") (pintype "unspecified"))
      (node (ref "Q4") (pin "3") (pinfunction "3_3") (pintype "input"))
    )
    (net (code "23") (name "Net-(NX1-Pad5)") (class "Default")
      (node (ref "NX1") (pin "5") (pinfunction "5_5") (pintype "unspecified"))
      (node (ref "NX2") (pin "5") (pinfunction "5_5") (pintype "unspecified"))
      (node (ref "Q5") (pin "3") (pinfunction "3_3") (pintype "input"))
    )
    (net (code "24") (name "Net-(NX1-Pad6)") (class "Default")
      (node (ref "NX1") (pin "6") (pinfunction "6_6") (pintype "unspecified"))
      (node (ref "NX2") (pin "6") (pinfunction "6_6") (pintype "unspecified"))
      (node (ref "Q6") (pin "3") (pinfunction "3_3") (pintype "input"))
    )
    (net (code "25") (name "Net-(NX1-Pad7)") (class "Default")
      (node (ref "NX1") (pin "7") (pinfunction "7_7") (pintype "unspecified"))
      (node (ref "NX2") (pin "7") (pinfunction "7_7") (pintype "unspecified"))
      (node (ref "Q7") (pin "3") (pinfunction "3_3") (pintype "input"))
    )
    (net (code "26") (name "Net-(NX1-Pad8)") (class "Default")
      (node (ref "NX1") (pin "8") (pinfunction "8_8") (pintype "unspecified"))
      (node (ref "NX2") (pin "8") (pinfunction "8_8") (pintype "unspecified"))
      (node (ref "Q8") (pin "3") (pinfunction "3_3") (pintype "input"))
    )
    (net (code "27") (name "Net-(NX1-Pad9)") (class "Default")
      (node (ref "NX1") (pin "9") (pinfunction "9_9") (pintype "unspecified"))
      (node (ref "NX2") (pin "9") (pinfunction "9_9") (pintype "unspecified"))
      (node (ref "Q9") (pin "3") (pinfunction "3_3") (pintype "input"))
    )
    (net (code "28") (name "Net-(NX1-PadA)") (class "Default")
      (node (ref "NX1") (pin "A") (pinfunction "A_A") (pintype "unspecified"))
      (node (ref "R1") (pin "1") (pinfunction "1_1") (pintype "unspecified"))
    )
    (net (code "29") (name "Net-(NX2-PadA)") (class "Default")
      (node (ref "NX2") (pin "A") (pinfunction "A_A") (pintype "unspecified"))
      (node (ref "R32") (pin "1") (pinfunction "1_1") (pintype "unspecified"))
    )
    (net (code "30") (name "Net-(NX3-11)") (class "Default")
      (node (ref "NX3") (pin "PR") (pinfunction "11_PR") (pintype "unspecified"))
      (node (ref "NX4") (pin "PR") (pinfunction "11_PR") (pintype "unspecified"))
      (node (ref "R56") (pin "2") (pinfunction "2_2") (pintype "unspecified"))
    )
    (net (code "31") (name "Net-(NX3-Pad0)") (class "Default")
      (node (ref "NX3") (pin "0") (pinfunction "0_0") (pintype "unspecified"))
      (node (ref "NX4") (pin "0") (pinfunction "0_0") (pintype "unspecified"))
      (node (ref "Q17") (pin "3") (pinfunction "3_3") (pintype "input"))
    )
    (net (code "32") (name "Net-(NX3-Pad1)") (class "Default")
      (node (ref "NX3") (pin "1") (pinfunction "1_1") (pintype "unspecified"))
      (node (ref "NX4") (pin "1") (pinfunction "1_1") (pintype "unspecified"))
      (node (ref "Q26") (pin "3") (pinfunction "3_3") (pintype "input"))
    )
    (net (code "33") (name "Net-(NX3-Pad2)") (class "Default")
      (node (ref "NX3") (pin "2") (pinfunction "2_2") (pintype "unspecified"))
      (node (ref "NX4") (pin "2") (pinfunction "2_2") (pintype "unspecified"))
      (node (ref "Q25") (pin "3") (pinfunction "3_3") (pintype "input"))
    )
    (net (code "34") (name "Net-(NX3-Pad3)") (class "Default")
      (node (ref "NX3") (pin "3") (pinfunction "3_3") (pintype "unspecified"))
      (node (ref "NX4") (pin "3") (pinfunction "3_3") (pintype "unspecified"))
      (node (ref "Q24") (pin "3") (pinfunction "3_3") (pintype "input"))
    )
    (net (code "35") (name "Net-(NX3-Pad4)") (class "Default")
      (node (ref "NX3") (pin "4") (pinfunction "4_4") (pintype "unspecified"))
      (node (ref "NX4") (pin "4") (pinfunction "4_4") (pintype "unspecified"))
      (node (ref "Q23") (pin "3") (pinfunction "3_3") (pintype "input"))
    )
    (net (code "36") (name "Net-(NX3-Pad5)") (class "Default")
      (node (ref "NX3") (pin "5") (pinfunction "5_5") (pintype "unspecified"))
      (node (ref "NX4") (pin "5") (pinfunction "5_5") (pintype "unspecified"))
      (node (ref "Q22") (pin "3") (pinfunction "3_3") (pintype "input"))
    )
    (net (code "37") (name "Net-(NX3-Pad6)") (class "Default")
      (node (ref "NX3") (pin "6") (pinfunction "6_6") (pintype "unspecified"))
      (node (ref "NX4") (pin "6") (pinfunction "6_6") (pintype "unspecified"))
      (node (ref "Q21") (pin "3") (pinfunction "3_3") (pintype "input"))
    )
    (net (code "38") (name "Net-(NX3-Pad7)") (class "Default")
      (node (ref "NX3") (pin "7") (pinfunction "7_7") (pintype "unspecified"))
      (node (ref "NX4") (pin "7") (pinfunction "7_7") (pintype "unspecified"))
      (node (ref "Q20") (pin "3") (pinfunction "3_3") (pintype "input"))
    )
    (net (code "39") (name "Net-(NX3-Pad8)") (class "Default")
      (node (ref "NX3") (pin "8") (pinfunction "8_8") (pintype "unspecified"))
      (node (ref "NX4") (pin "8") (pinfunction "8_8") (pintype "unspecified"))
      (node (ref "Q19") (pin "3") (pinfunction "3_3") (pintype "input"))
    )
    (net (code "40") (name "Net-(NX3-Pad9)") (class "Default")
      (node (ref "NX3") (pin "9") (pinfunction "9_9") (pintype "unspecified"))
      (node (ref "NX4") (pin "9") (pinfunction "9_9") (pintype "unspecified"))
      (node (ref "Q18") (pin "3") (pinfunction "3_3") (pintype "input"))
    )
    (net (code "41") (name "Net-(NX3-PadA)") (class "Default")
      (node (ref "NX3") (pin "A") (pinfunction "A_A") (pintype "unspecified"))
      (node (ref "R57") (pin "1") (pinfunction "1_1") (pintype "unspecified"))
    )
    (net (code "42") (name "Net-(NX4-PadA)") (class "Default")
      (node (ref "NX4") (pin "A") (pinfunction "A_A") (pintype "unspecified"))
      (node (ref "R58") (pin "1") (pinfunction "1_1") (pintype "unspecified"))
    )
    (net (code "43") (name "Net-(Q1-Pad1)") (class "Default")
      (node (ref "Q1") (pin "1") (pinfunction "1_1") (pintype "input"))
      (node (ref "R34") (pin "2") (pinfunction "2_2") (pintype "unspecified"))
    )
    (net (code "44") (name "Net-(Q2-Pad1)") (class "Default")
      (node (ref "Q2") (pin "1") (pinfunction "1_1") (pintype "input"))
      (node (ref "R35") (pin "2") (pinfunction "2_2") (pintype "unspecified"))
    )
    (net (code "45") (name "Net-(Q3-Pad1)") (class "Default")
      (node (ref "Q3") (pin "1") (pinfunction "1_1") (pintype "input"))
      (node (ref "R36") (pin "2") (pinfunction "2_2") (pintype "unspecified"))
    )
    (net (code "46") (name "Net-(Q4-Pad1)") (class "Default")
      (node (ref "Q4") (pin "1") (pinfunction "1_1") (pintype "input"))
      (node (ref "R37") (pin "2") (pinfunction "2_2") (pintype "unspecified"))
    )
    (net (code "47") (name "Net-(Q5-Pad1)") (class "Default")
      (node (ref "Q5") (pin "1") (pinfunction "1_1") (pintype "input"))
      (node (ref "R38") (pin "2") (pinfunction "2_2") (pintype "unspecified"))
    )
    (net (code "48") (name "Net-(Q6-Pad1)") (class "Default")
      (node (ref "Q6") (pin "1") (pinfunction "1_1") (pintype "input"))
      (node (ref "R39") (pin "2") (pinfunction "2_2") (pintype "unspecified"))
    )
    (net (code "49") (name "Net-(Q7-Pad1)") (class "Default")
      (node (ref "Q7") (pin "1") (pinfunction "1_1") (pintype "input"))
      (node (ref "R40") (pin "2") (pinfunction "2_2") (pintype "unspecified"))
    )
    (net (code "50") (name "Net-(Q8-Pad1)") (class "Default")
      (node (ref "Q8") (pin "1") (pinfunction "1_1") (pintype "input"))
      (node (ref "R41") (pin "2") (pinfunction "2_2") (pintype "unspecified"))
    )
    (net (code "51") (name "Net-(Q9-Pad1)") (class "Default")
      (node (ref "Q9") (pin "1") (pinfunction "1_1") (pintype "input"))
      (node (ref "R42") (pin "2") (pinfunction "2_2") (pintype "unspecified"))
    )
    (net (code "52") (name "Net-(Q10-Pad1)") (class "Default")
      (node (ref "Q10") (pin "1") (pinfunction "1_1") (pintype "input"))
      (node (ref "R43") (pin "2") (pinfunction "2_2") (pintype "unspecified"))
    )
    (net (code "53") (name "Net-(Q11-Pad1)") (class "Default")
      (node (ref "Q11") (pin "1") (pinfunction "1_1") (pintype "input"))
      (node (ref "R33") (pin "2") (pinfunction "2_2") (pintype "unspecified"))
    )
    (net (code "54") (name "Net-(Q11-Pad3)") (class "Default")
      (node (ref "Q11") (pin "3") (pinfunction "3_3") (pintype "input"))
      (node (ref "R55") (pin "1") (pinfunction "1_1") (pintype "unspecified"))
    )
    (net (code "55") (name "Net-(Q12-B)") (class "Default")
      (node (ref "Q12") (pin "1") (pinfunction "B_1") (pintype "unspecified"))
      (node (ref "R26") (pin "2") (pinfunction "2_2") (pintype "input"))
      (node (ref "R27") (pin "1") (pinfunction "1_1") (pintype "input"))
    )
    (net (code "56") (name "Net-(Q12-C)") (class "Default")
      (node (ref "Q12") (pin "3") (pinfunction "C_3") (pintype "unspecified"))
      (node (ref "TP8") (pin "1") (pinfunction "1_1") (pintype "unspecified"))
    )
    (net (code "57") (name "Net-(Q13-B)") (class "Default")
      (node (ref "Q13") (pin "1") (pinfunction "B_1") (pintype "unspecified"))
      (node (ref "R28") (pin "2") (pinfunction "2_2") (pintype "input"))
    )
    (net (code "58") (name "Net-(Q13-C)") (class "Default")
      (node (ref "Q13") (pin "3") (pinfunction "C_3") (pintype "unspecified"))
      (node (ref "R30") (pin "2") (pinfunction "2_2") (pintype "input"))
    )
    (net (code "59") (name "Net-(Q14-B)") (class "Default")
      (node (ref "Q14") (pin "1") (pinfunction "B_1") (pintype "unspecified"))
      (node (ref "R29") (pin "2") (pinfunction "2_2") (pintype "input"))
      (node (ref "R30") (pin "1") (pinfunction "1_1") (pintype "input"))
    )
    (net (code "60") (name "Net-(Q14-C)") (class "Default")
      (node (ref "Q14") (pin "3") (pinfunction "C_3") (pintype "unspecified"))
      (node (ref "TP9") (pin "1") (pinfunction "1_1") (pintype "unspecified"))
    )
    (net (code "61") (name "Net-(Q15-D)") (class "Default")
      (node (ref "Q15") (pin "3") (pinfunction "D_3") (pintype "unspecified"))
      (node (ref "R10") (pin "1") (pinfunction "1_1") (pintype "unspecified"))
      (node (ref "R11") (pin "1") (pinfunction "1_1") (pintype "unspecified"))
      (node (ref "R12") (pin "1") (pinfunction "1_1") (pintype "unspecified"))
      (node (ref "R13") (pin "1") (pinfunction "1_1") (pintype "unspecified"))
      (node (ref "R14") (pin "1") (pinfunction "1_1") (pintype "unspecified"))
    )
    (net (code "62") (name "Net-(Q15-G)") (class "Default")
      (node (ref "Q15") (pin "1") (pinfunction "G_1") (pintype "unspecified"))
      (node (ref "R8") (pin "2") (pinfunction "2_2") (pintype "input"))
      (node (ref "R9") (pin "2") (pinfunction "2_2") (pintype "unspecified"))
    )
    (net (code "63") (name "Net-(Q16-Pad1)") (class "Default")
      (node (ref "Q16") (pin "1") (pinfunction "1_1") (pintype "input"))
      (node (ref "R44") (pin "2") (pinfunction "2_2") (pintype "unspecified"))
    )
    (net (code "64") (name "Net-(Q16-Pad3)") (class "Default")
      (node (ref "Q16") (pin "3") (pinfunction "3_3") (pintype "input"))
      (node (ref "R56") (pin "1") (pinfunction "1_1") (pintype "unspecified"))
    )
    (net (code "65") (name "Net-(Q17-Pad1)") (class "Default")
      (node (ref "Q17") (pin "1") (pinfunction "1_1") (pintype "input"))
      (node (ref "R54") (pin "2") (pinfunction "2_2") (pintype "unspecified"))
    )
    (net (code "66") (name "Net-(Q18-Pad1)") (class "Default")
      (node (ref "Q18") (pin "1") (pinfunction "1_1") (pintype "input"))
      (node (ref "R53") (pin "2") (pinfunction "2_2") (pintype "unspecified"))
    )
    (net (code "67") (name "Net-(Q19-Pad1)") (class "Default")
      (node (ref "Q19") (pin "1") (pinfunction "1_1") (pintype "input"))
      (node (ref "R52") (pin "2") (pinfunction "2_2") (pintype "unspecified"))
    )
    (net (code "68") (name "Net-(Q20-Pad1)") (class "Default")
      (node (ref "Q20") (pin "1") (pinfunction "1_1") (pintype "input"))
      (node (ref "R51") (pin "2") (pinfunction "2_2") (pintype "unspecified"))
    )
    (net (code "69") (name "Net-(Q21-Pad1)") (class "Default")
      (node (ref "Q21") (pin "1") (pinfunction "1_1") (pintype "input"))
      (node (ref "R50") (pin "2") (pinfunction "2_2") (pintype "unspecified"))
    )
    (net (code "70") (name "Net-(Q22-Pad1)") (class "Default")
      (node (ref "Q22") (pin "1") (pinfunction "1_1") (pintype "input"))
      (node (ref "R49") (pin "2") (pinfunction "2_2") (pintype "unspecified"))
    )
    (net (code "71") (name "Net-(Q23-Pad1)") (class "Default")
      (node (ref "Q23") (pin "1") (pinfunction "1_1") (pintype "input"))
      (node (ref "R48") (pin "2") (pinfunction "2_2") (pintype "unspecified"))
    )
    (net (code "72") (name "Net-(Q24-Pad1)") (class "Default")
      (node (ref "Q24") (pin "1") (pinfunction "1_1") (pintype "input"))
      (node (ref "R47") (pin "2") (pinfunction "2_2") (pintype "unspecified"))
    )
    (net (code "73") (name "Net-(Q25-Pad1)") (class "Default")
      (node (ref "Q25") (pin "1") (pinfunction "1_1") (pintype "input"))
      (node (ref "R46") (pin "2") (pinfunction "2_2") (pintype "unspecified"))
    )
    (net (code "74") (name "Net-(Q26-Pad1)") (class "Default")
      (node (ref "Q26") (pin "1") (pinfunction "1_1") (pintype "input"))
      (node (ref "R45") (pin "2") (pinfunction "2_2") (pintype "unspecified"))
    )
    (net (code "75") (name "Net-(Q27-G)") (class "Default")
      (node (ref "Q27") (pin "1") (pinfunction "G_1") (pintype "unspecified"))
      (node (ref "R2") (pin "2") (pinfunction "2_2") (pintype "unspecified"))
      (node (ref "R3") (pin "2") (pinfunction "2_2") (pintype "input"))
    )
    (net (code "76") (name "Net-(Q28-B)") (class "Default")
      (node (ref "Q28") (pin "1") (pinfunction "B_1") (pintype "unspecified"))
      (node (ref "R25") (pin "2") (pinfunction "2_2") (pintype "input"))
    )
    (net (code "77") (name "Net-(Q28-C)") (class "Default")
      (node (ref "Q28") (pin "3") (pinfunction "C_3") (pintype "unspecified"))
      (node (ref "R27") (pin "2") (pinfunction "2_2") (pintype "input"))
    )
    (net (code "78") (name "Net-(U1-PB5{slash}SCKPCINT5)") (class "Default")
      (node (ref "TP3") (pin "1") (pinfunction "1_1") (pintype "unspecified"))
      (node (ref "U1") (pin "17") (pinfunction "PB5/SCKPCINT5_17") (pintype "unspecified"))
    )
    (net (code "79") (name "Net-(U1-PC0{slash}ADC0PCINT8)") (class "Default")
      (node (ref "R9") (pin "1") (pinfunction "1_1") (pintype "unspecified"))
      (node (ref "U1") (pin "23") (pinfunction "PC0/ADC0PCINT8_23") (pintype "unspecified"))
    )
    (net (code "80") (name "Net-(U1-PC1{slash}ADC1PCINT9)") (class "Default")
      (node (ref "R2") (pin "1") (pinfunction "1_1") (pintype "unspecified"))
      (node (ref "U1") (pin "24") (pinfunction "PC1/ADC1PCINT9_24") (pintype "unspecified"))
    )
    (net (code "81") (name "Net-(U1-PC4{slash}ADC4SDAPCINT12)") (class "Default")
      (node (ref "U1") (pin "27") (pinfunction "PC4/ADC4SDAPCINT12_27") (pintype "unspecified"))
      (node (ref "U2") (pin "7") (pinfunction "SDA_7") (pintype "unspecified"))
      (node (ref "U3") (pin "6") (pinfunction "SDA_6") (pintype "unspecified"))
    )
    (net (code "82") (name "Net-(U1-PC5{slash}ADC5SCLPCINT13)") (class "Default")
      (node (ref "U1") (pin "28") (pinfunction "PC5/ADC5SCLPCINT13_28") (pintype "unspecified"))
      (node (ref "U2") (pin "8") (pinfunction "SCL_8") (pintype "unspecified"))
      (node (ref "U3") (pin "4") (pinfunction "SCL_4") (pintype "unspecified"))
    )
    (net (code "83") (name "Net-(U1-PC6{slash}RESETPCINT14)") (class "Default")
      (node (ref "C2") (pin "2") (pinfunction "2_2") (pintype "unspecified"))
      (node (ref "R5") (pin "1") (pinfunction "1_1") (pintype "input"))
      (node (ref "TP1") (pin "1") (pinfunction "1_1") (pintype "unspecified"))
      (node (ref "U1") (pin "29") (pinfunction "PC6/RESETPCINT14_29") (pintype "unspecified"))
    )
    (net (code "84") (name "Net-(U1-PD0{slash}RXDPCINT16)") (class "Default")
      (node (ref "SW3") (pin "1") (pinfunction "1_1") (pintype "unspecified"))
      (node (ref "U1") (pin "30") (pinfunction "PD0/RXDPCINT16_30") (pintype "unspecified"))
    )
    (net (code "85") (name "Net-(U1-PD1{slash}TXDPCINT17)") (class "Default")
      (node (ref "SW1") (pin "1") (pinfunction "1_1") (pintype "unspecified"))
      (node (ref "U1") (pin "31") (pinfunction "PD1/TXDPCINT17_31") (pintype "unspecified"))
    )
    (net (code "86") (name "Net-(U1-PD2{slash}INT0PCINT18)") (class "Default")
      (node (ref "SW2") (pin "1") (pinfunction "1_1") (pintype "unspecified"))
      (node (ref "U1") (pin "32") (pinfunction "PD2/INT0PCINT18_32") (pintype "unspecified"))
    )
    (net (code "87") (name "Net-(U1-{slash}PCINT3OC2AMOSI{slash}PB3)") (class "Default")
      (node (ref "TP5") (pin "1") (pinfunction "1_1") (pintype "unspecified"))
      (node (ref "U1") (pin "15") (pinfunction "/PCINT3OC2AMOSI/PB3_15") (pintype "unspecified"))
    )
    (net (code "88") (name "Net-(U1-{slash}PCINT4MISO{slash}PB4)") (class "Default")
      (node (ref "TP4") (pin "1") (pinfunction "1_1") (pintype "unspecified"))
      (node (ref "U1") (pin "16") (pinfunction "/PCINT4MISO/PB4_16") (pintype "unspecified"))
    )
    (net (code "89") (name "Net-(U1-{slash}PCINT21OC0BT1{slash}PD5)") (class "Default")
      (node (ref "U1") (pin "9") (pinfunction "/PCINT21OC0BT1/PD5_9") (pintype "unspecified"))
      (node (ref "U7") (pin "12") (pinfunction "RCLK_12") (pintype "unspecified"))
      (node (ref "U8") (pin "12") (pinfunction "RCLK_12") (pintype "unspecified"))
      (node (ref "U9") (pin "12") (pinfunction "RCLK_12") (pintype "unspecified"))
    )
    (net (code "90") (name "Net-(U1-{slash}PCINT22OC0AAIN0{slash}PD6)") (class "Default")
      (node (ref "U1") (pin "10") (pinfunction "/PCINT22OC0AAIN0/PD6_10") (pintype "unspecified"))
      (node (ref "U7") (pin "11") (pinfunction "SRCLK_11") (pintype "unspecified"))
      (node (ref "U8") (pin "11") (pinfunction "SRCLK_11") (pintype "unspecified"))
      (node (ref "U9") (pin "11") (pinfunction "SRCLK_11") (pintype "unspecified"))
    )
    (net (code "91") (name "Net-(U1-{slash}PCINT23AIN1{slash}PD7)") (class "Default")
      (node (ref "U1") (pin "11") (pinfunction "/PCINT23AIN1/PD7_11") (pintype "unspecified"))
      (node (ref "U7") (pin "14") (pinfunction "SER_14") (pintype "unspecified"))
    )
    (net (code "92") (name "Net-(U2-VBAT)") (class "Default")
      (node (ref "C1") (pin "1") (pinfunction "1_1") (pintype "unspecified"))
      (node (ref "D1") (pin "1") (pinfunction "1_1") (pintype "unspecified"))
      (node (ref "U2") (pin "6") (pinfunction "VBAT_6") (pintype "unspecified"))
    )
    (net (code "93") (name "Net-(U7-QH#)") (class "Default")
      (node (ref "U7") (pin "9") (pinfunction "QH#_9") (pintype "unspecified"))
      (node (ref "U8") (pin "14") (pinfunction "SER_14") (pintype "unspecified"))
    )
    (net (code "94") (name "Net-(U8-QH#)") (class "Default")
      (node (ref "U8") (pin "9") (pinfunction "QH#_9") (pintype "unspecified"))
      (node (ref "U9") (pin "14") (pinfunction "SER_14") (pintype "unspecified"))
    )
    (net (code "95") (name "unconnected-(BUZZER-Pad3)") (class "Default")
      (node (ref "BUZZER") (pin "3") (pinfunction "3_3") (pintype "unspecified"))
    )
    (net (code "96") (name "unconnected-(R33-Pad1)") (class "Default")
      (node (ref "R33") (pin "1") (pinfunction "1_1") (pintype "unspecified"))
    )
    (net (code "97") (name "unconnected-(R34-Pad1)") (class "Default")
      (node (ref "R34") (pin "1") (pinfunction "1_1") (pintype "unspecified"))
    )
    (net (code "98") (name "unconnected-(R35-Pad1)") (class "Default")
      (node (ref "R35") (pin "1") (pinfunction "1_1") (pintype "unspecified"))
    )
    (net (code "99") (name "unconnected-(R36-Pad1)") (class "Default")
      (node (ref "R36") (pin "1") (pinfunction "1_1") (pintype "unspecified"))
    )
    (net (code "100") (name "unconnected-(R37-Pad1)") (class "Default")
      (node (ref "R37") (pin "1") (pinfunction "1_1") (pintype "unspecified"))
    )
    (net (code "101") (name "unconnected-(R38-Pad1)") (class "Default")
      (node (ref "R38") (pin "1") (pinfunction "1_1") (pintype "unspecified"))
    )
    (net (code "102") (name "unconnected-(R39-Pad1)") (class "Default")
      (node (ref "R39") (pin "1") (pinfunction "1_1") (pintype "unspecified"))
    )
    (net (code "103") (name "unconnected-(R40-Pad1)") (class "Default")
      (node (ref "R40") (pin "1") (pinfunction "1_1") (pintype "unspecified"))
    )
    (net (code "104") (name "unconnected-(R41-Pad1)") (class "Default")
      (node (ref "R41") (pin "1") (pinfunction "1_1") (pintype "unspecified"))
    )
    (net (code "105") (name "unconnected-(R42-Pad1)") (class "Default")
      (node (ref "R42") (pin "1") (pinfunction "1_1") (pintype "unspecified"))
    )
    (net (code "106") (name "unconnected-(R43-Pad1)") (class "Default")
      (node (ref "R43") (pin "1") (pinfunction "1_1") (pintype "unspecified"))
    )
    (net (code "107") (name "unconnected-(R44-Pad1)") (class "Default")
      (node (ref "R44") (pin "1") (pinfunction "1_1") (pintype "unspecified"))
    )
    (net (code "108") (name "unconnected-(R45-Pad1)") (class "Default")
      (node (ref "R45") (pin "1") (pinfunction "1_1") (pintype "unspecified"))
    )
    (net (code "109") (name "unconnected-(R46-Pad1)") (class "Default")
      (node (ref "R46") (pin "1") (pinfunction "1_1") (pintype "unspecified"))
    )
    (net (code "110") (name "unconnected-(R47-Pad1)") (class "Default")
      (node (ref "R47") (pin "1") (pinfunction "1_1") (pintype "unspecified"))
    )
    (net (code "111") (name "unconnected-(R48-Pad1)") (class "Default")
      (node (ref "R48") (pin "1") (pinfunction "1_1") (pintype "unspecified"))
    )
    (net (code "112") (name "unconnected-(R49-Pad1)") (class "Default")
      (node (ref "R49") (pin "1") (pinfunction "1_1") (pintype "unspecified"))
    )
    (net (code "113") (name "unconnected-(R50-Pad1)") (class "Default")
      (node (ref "R50") (pin "1") (pinfunction "1_1") (pintype "unspecified"))
    )
    (net (code "114") (name "unconnected-(R51-Pad1)") (class "Default")
      (node (ref "R51") (pin "1") (pinfunction "1_1") (pintype "unspecified"))
    )
    (net (code "115") (name "unconnected-(R52-Pad1)") (class "Default")
      (node (ref "R52") (pin "1") (pinfunction "1_1") (pintype "unspecified"))
    )
    (net (code "116") (name "unconnected-(R53-Pad1)") (class "Default")
      (node (ref "R53") (pin "1") (pinfunction "1_1") (pintype "unspecified"))
    )
    (net (code "117") (name "unconnected-(R54-Pad1)") (class "Default")
      (node (ref "R54") (pin "1") (pinfunction "1_1") (pintype "unspecified"))
    )
    (net (code "118") (name "unconnected-(SW1-Pad3)") (class "Default")
      (node (ref "SW1") (pin "3") (pinfunction "3_3") (pintype "unspecified"))
    )
    (net (code "119") (name "unconnected-(SW2-Pad3)") (class "Default")
      (node (ref "SW2") (pin "3") (pinfunction "3_3") (pintype "unspecified"))
    )
    (net (code "120") (name "unconnected-(SW3-Pad3)") (class "Default")
      (node (ref "SW3") (pin "3") (pinfunction "3_3") (pintype "unspecified"))
    )
    (net (code "121") (name "unconnected-(U1-ADC6-Pad19)") (class "Default")
      (node (ref "U1") (pin "19") (pinfunction "ADC6_19") (pintype "input"))
    )
    (net (code "122") (name "unconnected-(U1-ADC7-Pad22)") (class "Default")
      (node (ref "U1") (pin "22") (pinfunction "ADC7_22") (pintype "input"))
    )
    (net (code "123") (name "unconnected-(U1-AREF-Pad20)") (class "Default")
      (node (ref "U1") (pin "20") (pinfunction "AREF_20") (pintype "input"))
    )
    (net (code "124") (name "unconnected-(U1-PC2{slash}ADC2PCINT10-Pad25)") (class "Default")
      (node (ref "U1") (pin "25") (pinfunction "PC2/ADC2PCINT10_25") (pintype "unspecified"))
    )
    (net (code "125") (name "unconnected-(U1-PC3{slash}ADC3PCINT11-Pad26)") (class "Default")
      (node (ref "U1") (pin "26") (pinfunction "PC3/ADC3PCINT11_26") (pintype "unspecified"))
    )
    (net (code "126") (name "unconnected-(U1-{slash}PCINT0CLKOICP1{slash}PB0-Pad12)") (class "Default")
      (node (ref "U1") (pin "12") (pinfunction "/PCINT0CLKOICP1/PB0_12") (pintype "unspecified"))
    )
    (net (code "127") (name "unconnected-(U1-{slash}PCINT1OC1A{slash}PB1-Pad13)") (class "Default")
      (node (ref "U1") (pin "13") (pinfunction "/PCINT1OC1A/PB1_13") (pintype "unspecified"))
    )
    (net (code "128") (name "unconnected-(U1-{slash}PCINT2SSOC1B{slash}PB2-Pad14)") (class "Default")
      (node (ref "U1") (pin "14") (pinfunction "/PCINT2SSOC1B/PB2_14") (pintype "unspecified"))
    )
    (net (code "129") (name "unconnected-(U2-32KHZ-Pad1)") (class "Default")
      (node (ref "U2") (pin "1") (pinfunction "32KHZ_1") (pintype "unspecified"))
    )
    (net (code "130") (name "unconnected-(U2-INT#{slash}SQW-Pad3)") (class "Default")
      (node (ref "U2") (pin "3") (pinfunction "INT#/SQW_3") (pintype "unspecified"))
    )
    (net (code "131") (name "unconnected-(U2-RST#-Pad4)") (class "Default")
      (node (ref "U2") (pin "4") (pinfunction "RST#_4") (pintype "unspecified"))
    )
    (net (code "132") (name "unconnected-(U3-EP-Pad7)") (class "Default")
      (node (ref "U3") (pin "7") (pinfunction "EP_7") (pintype "unspecified"))
    )
    (net (code "133") (name "unconnected-(U3-INT-Pad5)") (class "Default")
      (node (ref "U3") (pin "5") (pinfunction "INT_5") (pintype "unspecified"))
    )
    (net (code "134") (name "unconnected-(U7-QA-Pad15)") (class "Default")
      (node (ref "U7") (pin "15") (pinfunction "QA_15") (pintype "unspecified"))
    )
    (net (code "135") (name "unconnected-(U7-QB-Pad1)") (class "Default")
      (node (ref "U7") (pin "1") (pinfunction "QB_1") (pintype "unspecified"))
    )
    (net (code "136") (name "unconnected-(U7-QC-Pad2)") (class "Default")
      (node (ref "U7") (pin "2") (pinfunction "QC_2") (pintype "unspecified"))
    )
    (net (code "137") (name "unconnected-(U7-QD-Pad3)") (class "Default")
      (node (ref "U7") (pin "3") (pinfunction "QD_3") (pintype "unspecified"))
    )
    (net (code "138") (name "unconnected-(U7-QE-Pad4)") (class "Default")
      (node (ref "U7") (pin "4") (pinfunction "QE_4") (pintype "unspecified"))
    )
    (net (code "139") (name "unconnected-(U7-QF-Pad5)") (class "Default")
      (node (ref "U7") (pin "5") (pinfunction "QF_5") (pintype "unspecified"))
    )
    (net (code "140") (name "unconnected-(U7-QG-Pad6)") (class "Default")
      (node (ref "U7") (pin "6") (pinfunction "QG_6") (pintype "unspecified"))
    )
    (net (code "141") (name "unconnected-(U7-QH-Pad7)") (class "Default")
      (node (ref "U7") (pin "7") (pinfunction "QH_7") (pintype "unspecified"))
    )
    (net (code "142") (name "unconnected-(U8-QA-Pad15)") (class "Default")
      (node (ref "U8") (pin "15") (pinfunction "QA_15") (pintype "unspecified"))
    )
    (net (code "143") (name "unconnected-(U8-QB-Pad1)") (class "Default")
      (node (ref "U8") (pin "1") (pinfunction "QB_1") (pintype "unspecified"))
    )
    (net (code "144") (name "unconnected-(U8-QC-Pad2)") (class "Default")
      (node (ref "U8") (pin "2") (pinfunction "QC_2") (pintype "unspecified"))
    )
    (net (code "145") (name "unconnected-(U8-QD-Pad3)") (class "Default")
      (node (ref "U8") (pin "3") (pinfunction "QD_3") (pintype "unspecified"))
    )
    (net (code "146") (name "unconnected-(U8-QE-Pad4)") (class "Default")
      (node (ref "U8") (pin "4") (pinfunction "QE_4") (pintype "unspecified"))
    )
    (net (code "147") (name "unconnected-(U8-QF-Pad5)") (class "Default")
      (node (ref "U8") (pin "5") (pinfunction "QF_5") (pintype "unspecified"))
    )
    (net (code "148") (name "unconnected-(U8-QG-Pad6)") (class "Default")
      (node (ref "U8") (pin "6") (pinfunction "QG_6") (pintype "unspecified"))
    )
    (net (code "149") (name "unconnected-(U8-QH-Pad7)") (class "Default")
      (node (ref "U8") (pin "7") (pinfunction "QH_7") (pintype "unspecified"))
    )
    (net (code "150") (name "unconnected-(U9-QA-Pad15)") (class "Default")
      (node (ref "U9") (pin "15") (pinfunction "QA_15") (pintype "unspecified"))
    )
    (net (code "151") (name "unconnected-(U9-QB-Pad1)") (class "Default")
      (node (ref "U9") (pin "1") (pinfunction "QB_1") (pintype "unspecified"))
    )
    (net (code "152") (name "unconnected-(U9-QC-Pad2)") (class "Default")
      (node (ref "U9") (pin "2") (pinfunction "QC_2") (pintype "unspecified"))
    )
    (net (code "153") (name "unconnected-(U9-QD-Pad3)") (class "Default")
      (node (ref "U9") (pin "3") (pinfunction "QD_3") (pintype "unspecified"))
    )
    (net (code "154") (name "unconnected-(U9-QE-Pad4)") (class "Default")
      (node (ref "U9") (pin "4") (pinfunction "QE_4") (pintype "unspecified"))
    )
    (net (code "155") (name "unconnected-(U9-QF-Pad5)") (class "Default")
      (node (ref "U9") (pin "5") (pinfunction "QF_5") (pintype "unspecified"))
    )
    (net (code "156") (name "unconnected-(U9-QG-Pad6)") (class "Default")
      (node (ref "U9") (pin "6") (pinfunction "QG_6") (pintype "unspecified"))
    )
    (net (code "157") (name "unconnected-(U9-QH#-Pad9)") (class "Default")
      (node (ref "U9") (pin "9") (pinfunction "QH#_9") (pintype "unspecified"))
    )
    (net (code "158") (name "unconnected-(U9-QH-Pad7)") (class "Default")
      (node (ref "U9") (pin "7") (pinfunction "QH_7") (pintype "unspecified"))
    )
    (net (code "159") (name "unconnected-(USB1-CC1-PadA5)") (class "Default")
      (node (ref "USB1") (pin "A5") (pinfunction "CC1_A5") (pintype "unspecified"))
    )
    (net (code "160") (name "unconnected-(USB1-CC2-PadB5)") (class "Default")
      (node (ref "USB1") (pin "B5") (pinfunction "CC2_B5") (pintype "unspecified"))
    )
    (net (code "161") (name "unconnected-(USB1-Pad1)") (class "Default")
      (node (ref "USB1") (pin "1") (pinfunction "1_1") (pintype "unspecified"))
    )
    (net (code "162") (name "unconnected-(USB1-Pad2)") (class "Default")
      (node (ref "USB1") (pin "2") (pinfunction "2_2") (pintype "unspecified"))
    )
    (net (code "163") (name "unconnected-(USB1-Pad3)") (class "Default")
      (node (ref "USB1") (pin "3") (pinfunction "3_3") (pintype "unspecified"))
    )
    (net (code "164") (name "unconnected-(USB1-Pad4)") (class "Default")
      (node (ref "USB1") (pin "4") (pinfunction "4_4") (pintype "unspecified"))
    )
  )
)
